# Compressor.net
KiCad netlist of a schematic drawn in Altium Designer
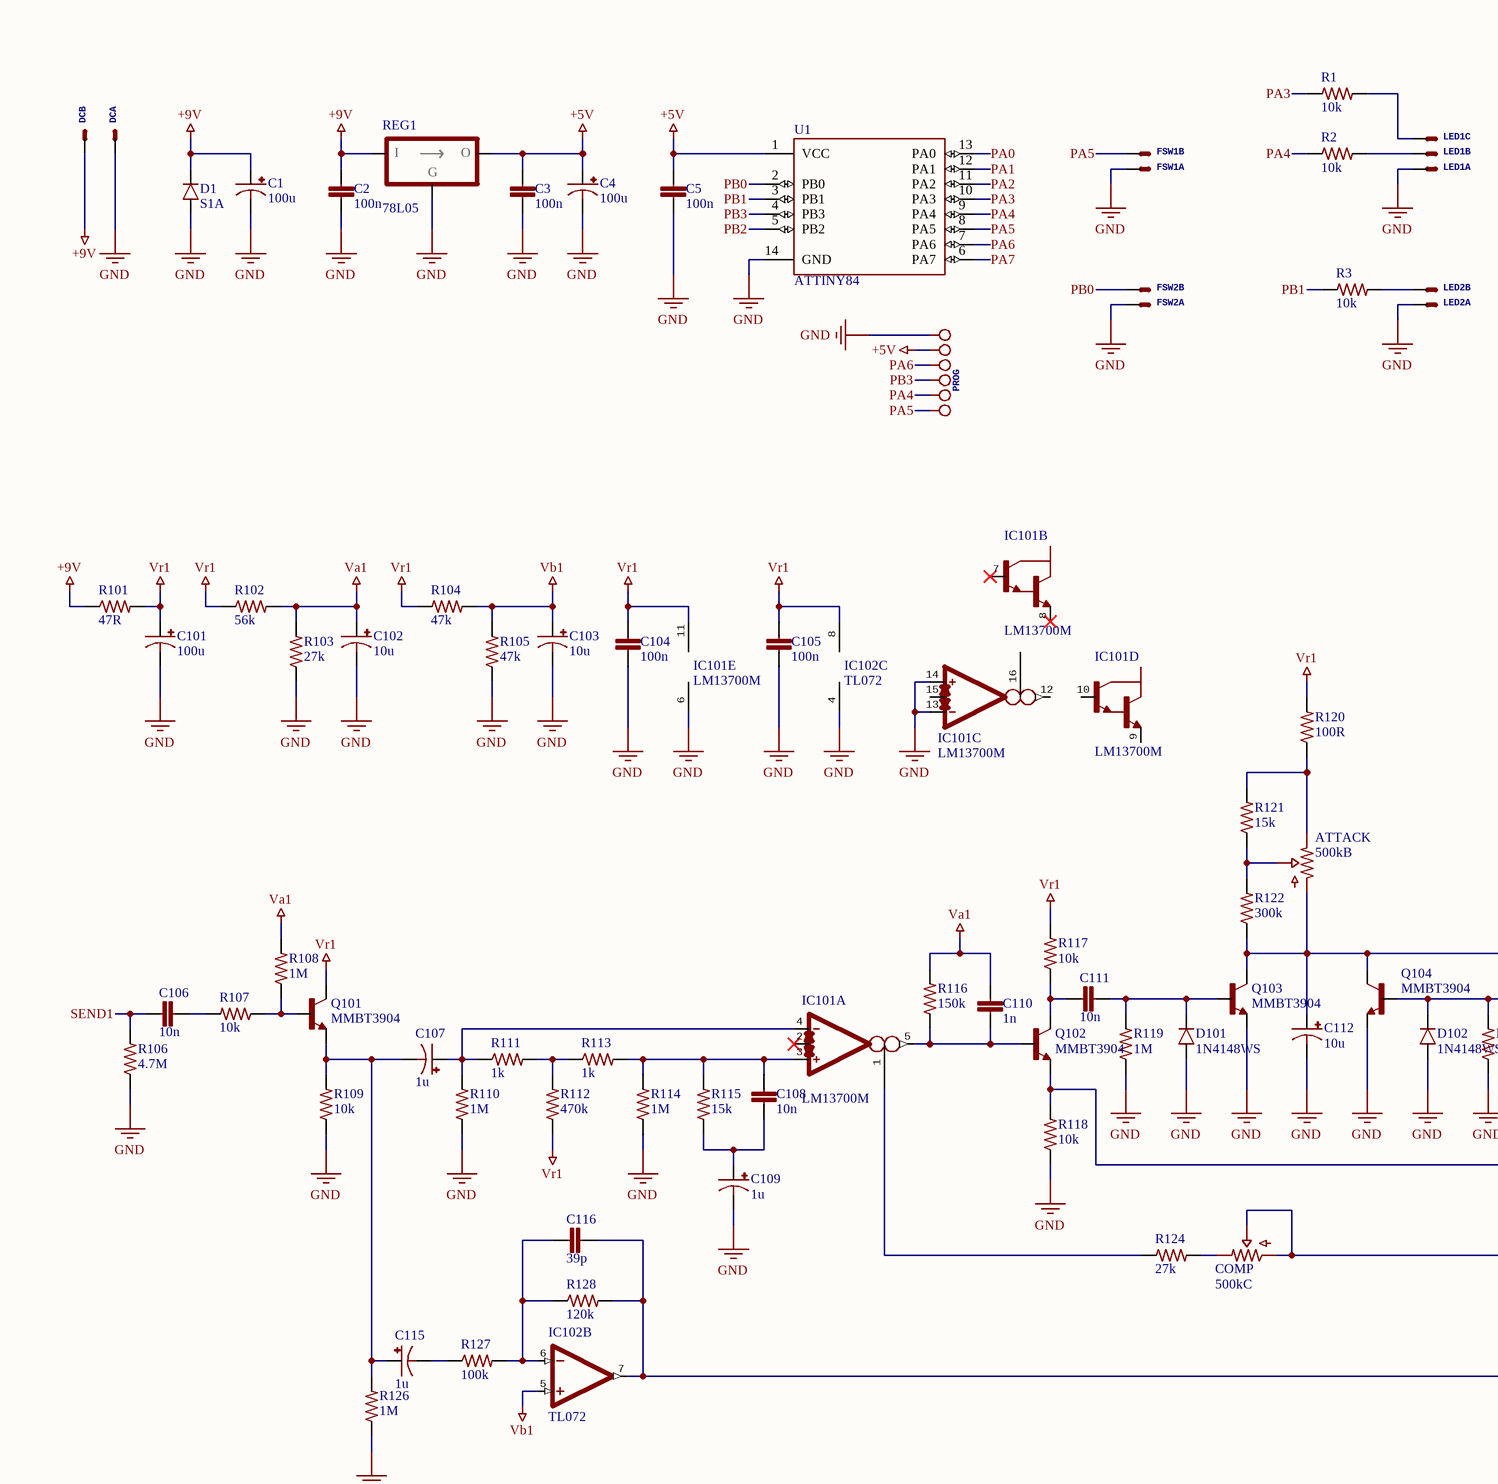
[diagram p0: Compressor.SchDoc, top left]
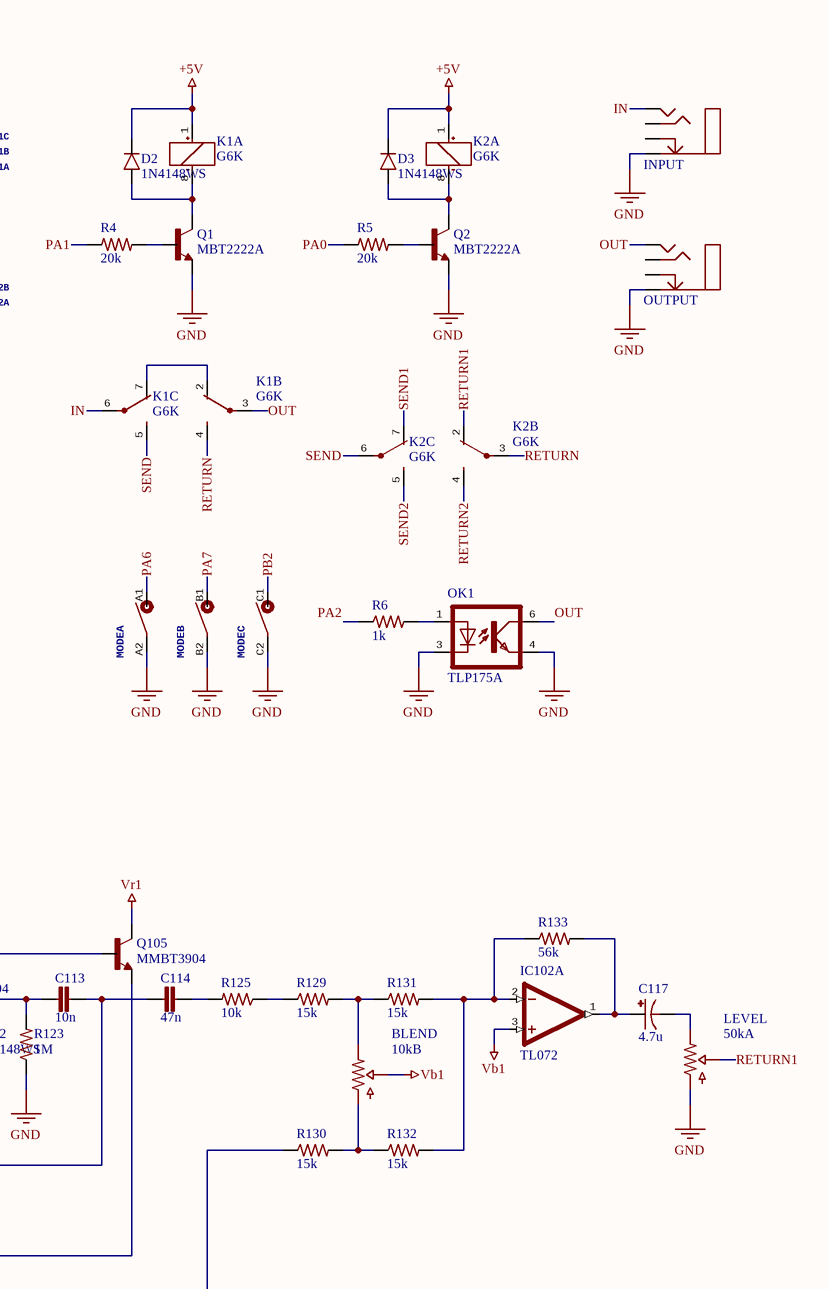
[diagram p1: Compressor.SchDoc, top right]
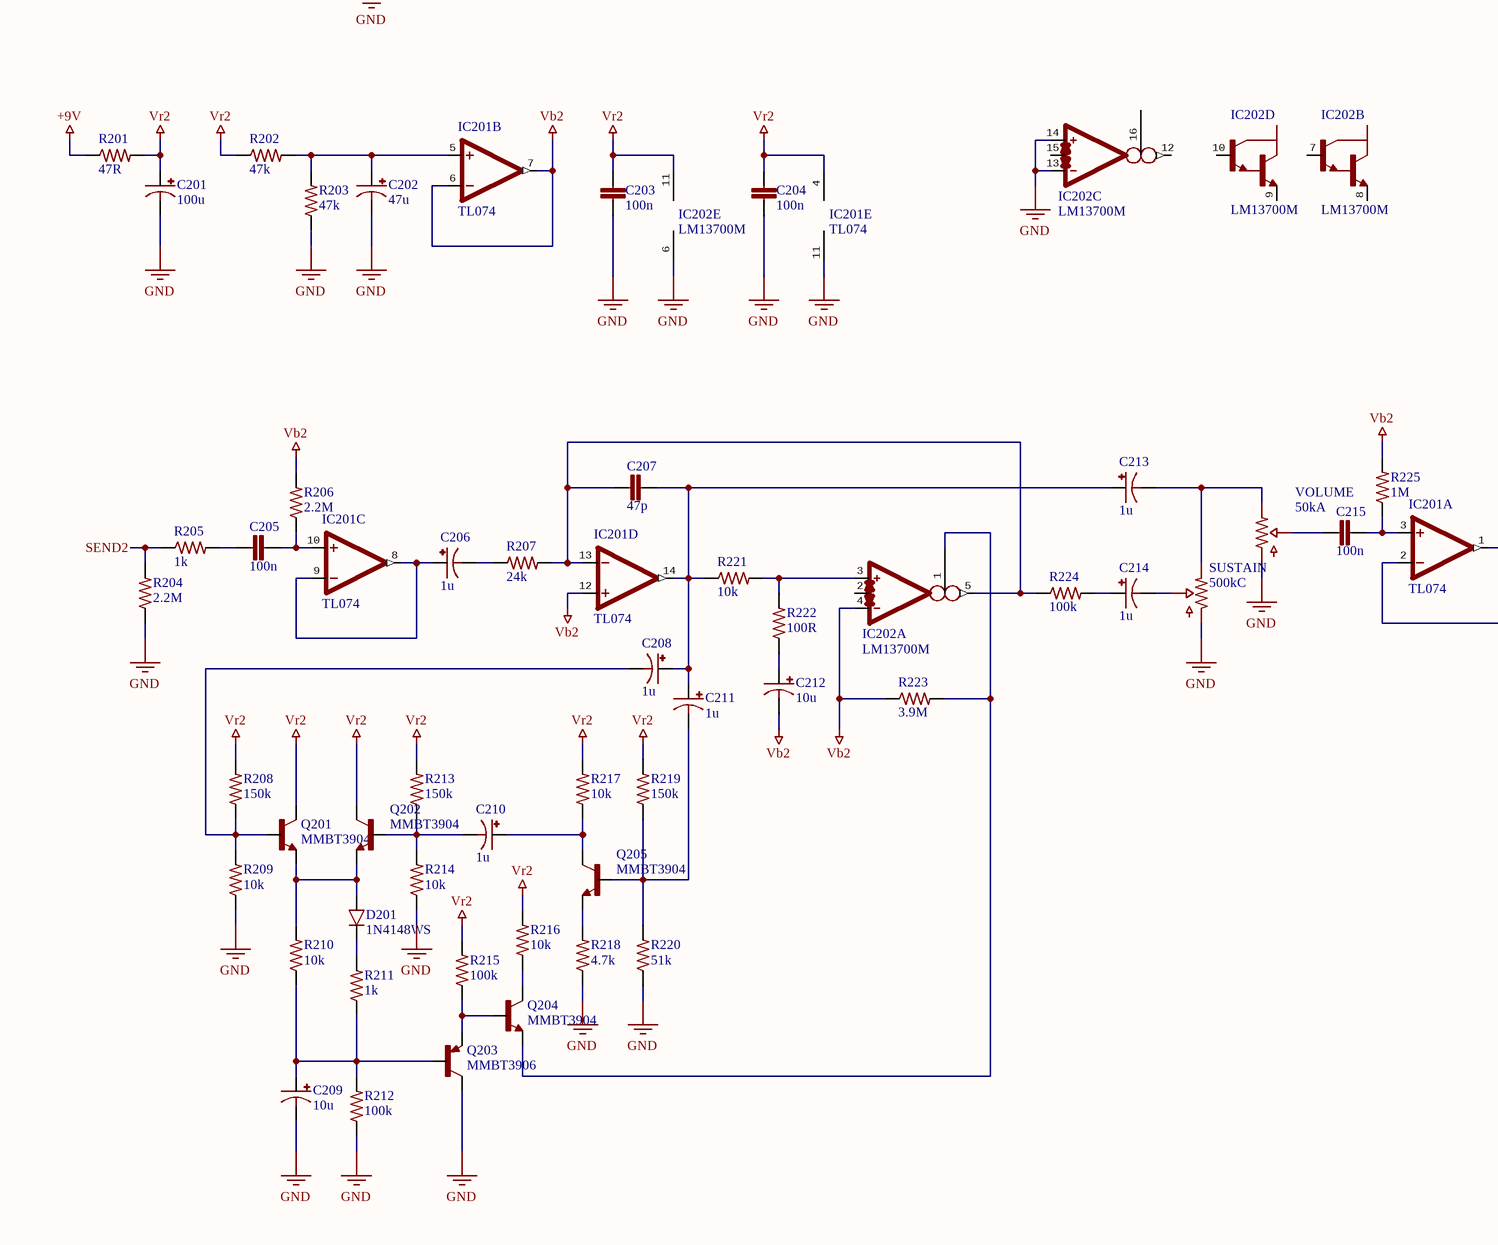
[diagram p2: Compressor.SchDoc, bottom left]
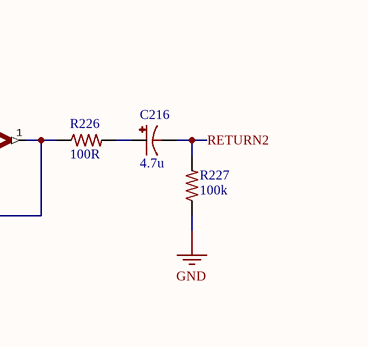
[diagram p3: Compressor.SchDoc, bottom right]

(export (version "E")
  (design (tool "Eeschema 10.0.6"))
  (components
    (comp (ref "ATTACK")
      (value "500kB")
      (footprint "ALPHA_9MM_TOP_NOMH")
      (description "500k Lin potentiometer round shaft")
      (libsource (lib "Pedals") (part "POT_500kB_ALPHA_9mm"))
    )
    (comp (ref "BLEND")
      (value "10kB")
      (footprint "ALPHA_9MM_TOP_NOMH")
      (description "10k Lin potentiometer round shaft")
      (libsource (lib "Pedals") (part "POT_10kB_ALPHA_9mm"))
    )
    (comp (ref "C1")
      (value "100u")
      (footprint "CAPAE_D")
      (description "CAP ALUM 100UF 25V SMD")
      (fields
        (field (name "MANUFACTURER") "Multicomp")
        (field (name "MANUFACTURER PART NUMBER") "MCVVT025M101EA6L")
      )
      (libsource (lib "Pedals SMD") (part "MCVVT025M101EA6L"))
    )
    (comp (ref "C2")
      (value "100n")
      (footprint "CHIP_0603")
      (description "CAP CER 100NF 50V X7R 0603")
      (fields
        (field (name "MANUFACTURER") "Multicomp")
        (field (name "MANUFACTURER PART NUMBER") "MC0603B104K500CT")
      )
      (libsource (lib "Pedals SMD") (part "MC0603B104K500CT"))
    )
    (comp (ref "C3")
      (value "100n")
      (footprint "CHIP_0603")
      (description "CAP CER 100NF 50V X7R 0603")
      (fields
        (field (name "MANUFACTURER") "Multicomp")
        (field (name "MANUFACTURER PART NUMBER") "MC0603B104K500CT")
      )
      (libsource (lib "Pedals SMD") (part "MC0603B104K500CT"))
    )
    (comp (ref "C4")
      (value "100u")
      (footprint "CAPAE_D")
      (description "CAP ALUM 100UF 25V SMD")
      (fields
        (field (name "MANUFACTURER") "Multicomp")
        (field (name "MANUFACTURER PART NUMBER") "MCVVT025M101EA6L")
      )
      (libsource (lib "Pedals SMD") (part "MCVVT025M101EA6L"))
    )
    (comp (ref "C5")
      (value "100n")
      (footprint "CHIP_0603")
      (description "CAP CER 100NF 50V X7R 0603")
      (fields
        (field (name "MANUFACTURER") "Multicomp")
        (field (name "MANUFACTURER PART NUMBER") "MC0603B104K500CT")
      )
      (libsource (lib "Pedals SMD") (part "MC0603B104K500CT"))
    )
    (comp (ref "C101")
      (value "100u")
      (footprint "CAPAE_D")
      (description "CAP ALUM 100UF 25V SMD")
      (fields
        (field (name "MANUFACTURER") "Multicomp")
        (field (name "MANUFACTURER PART NUMBER") "MCVVT025M101EA6L")
      )
      (libsource (lib "Pedals SMD") (part "MCVVT025M101EA6L"))
    )
    (comp (ref "C102")
      (value "10u")
      (footprint "CAPAE_B")
      (description "CAP ALUM 10UF 25V SMD")
      (fields
        (field (name "MANUFACTURER") "Multicomp")
        (field (name "MANUFACTURER PART NUMBER") "MCVVT025M100CA1L")
      )
      (libsource (lib "Pedals SMD") (part "MCVVT025M100CA1L"))
    )
    (comp (ref "C103")
      (value "10u")
      (footprint "CAPAE_B")
      (description "CAP ALUM 10UF 25V SMD")
      (fields
        (field (name "MANUFACTURER") "Multicomp")
        (field (name "MANUFACTURER PART NUMBER") "MCVVT025M100CA1L")
      )
      (libsource (lib "Pedals SMD") (part "MCVVT025M100CA1L"))
    )
    (comp (ref "C104")
      (value "100n")
      (footprint "CHIP_0603")
      (description "CAP CER 100NF 50V X7R 0603")
      (fields
        (field (name "MANUFACTURER") "Multicomp")
        (field (name "MANUFACTURER PART NUMBER") "MC0603B104K500CT")
      )
      (libsource (lib "Pedals SMD") (part "MC0603B104K500CT"))
    )
    (comp (ref "C105")
      (value "100n")
      (footprint "CHIP_0603")
      (description "CAP CER 100NF 50V X7R 0603")
      (fields
        (field (name "MANUFACTURER") "Multicomp")
        (field (name "MANUFACTURER PART NUMBER") "MC0603B104K500CT")
      )
      (libsource (lib "Pedals SMD") (part "MC0603B104K500CT"))
    )
    (comp (ref "C106")
      (value "10n")
      (footprint "CHIP_0603")
      (description "CAP CER 10NF 50V C0G/NP0 0603")
      (fields
        (field (name "MANUFACTURER") "Murata")
        (field (name "MANUFACTURER PART NUMBER") "GRM1885C1H103JA01D")
      )
      (libsource (lib "Pedals SMD") (part "GRM1885C1H103JA01D"))
    )
    (comp (ref "C107")
      (value "1u")
      (footprint "CAPAE_B")
      (description "CAP ALUM 1UF 50V LESR SMD")
      (fields
        (field (name "MANUFACTURER") "Panasonic")
        (field (name "MANUFACTURER PART NUMBER") "EEEFC1H1R0R")
      )
      (libsource (lib "") (part "EEEFC1H1R0R_1"))
    )
    (comp (ref "C108")
      (value "10n")
      (footprint "CHIP_0603")
      (description "CAP CER 10NF 50V C0G/NP0 0603")
      (fields
        (field (name "MANUFACTURER") "Murata")
        (field (name "MANUFACTURER PART NUMBER") "GRM1885C1H103JA01D")
      )
      (libsource (lib "") (part "GRM1885C1H103JA01D_1"))
    )
    (comp (ref "C109")
      (value "1u")
      (footprint "TAN_1206")
      (description "CAP TANT 1UF 16V")
      (fields
        (field (name "MANUFACTURER") "KEMET")
        (field (name "MANUFACTURER PART NUMBER") "T491A105K016AT")
      )
      (libsource (lib "Pedals SMD") (part "T491A105K016AT"))
    )
    (comp (ref "C110")
      (value "1n")
      (footprint "CHIP_0603")
      (description "CAP CER 1NF 50V C0G/NP0 0603")
      (fields
        (field (name "MANUFACTURER") "Murata")
        (field (name "MANUFACTURER PART NUMBER") "GRM1885C1H102JA01D")
      )
      (libsource (lib "Pedals SMD") (part "GRM1885C1H102JA01D"))
    )
    (comp (ref "C111")
      (value "10n")
      (footprint "CHIP_0603")
      (description "CAP CER 10NF 50V C0G/NP0 0603")
      (fields
        (field (name "MANUFACTURER") "Murata")
        (field (name "MANUFACTURER PART NUMBER") "GRM1885C1H103JA01D")
      )
      (libsource (lib "Pedals SMD") (part "GRM1885C1H103JA01D"))
    )
    (comp (ref "C112")
      (value "10u")
      (footprint "TAN_1206")
      (description "CAP TANT 10UF 16V")
      (fields
        (field (name "MANUFACTURER") "KEMET")
        (field (name "MANUFACTURER PART NUMBER") "T491A106K016AT")
      )
      (libsource (lib "Pedals SMD") (part "T491A106K016AT"))
    )
    (comp (ref "C113")
      (value "10n")
      (footprint "CHIP_0603")
      (description "CAP CER 10NF 50V C0G/NP0 0603")
      (fields
        (field (name "MANUFACTURER") "Murata")
        (field (name "MANUFACTURER PART NUMBER") "GRM1885C1H103JA01D")
      )
      (libsource (lib "Pedals SMD") (part "GRM1885C1H103JA01D"))
    )
    (comp (ref "C114")
      (value "47n")
      (footprint "CHIP_1206")
      (description "CAP CER 47NF 50V C0G/NP0 1206")
      (fields
        (field (name "MANUFACTURER") "Murata")
        (field (name "MANUFACTURER PART NUMBER") "GCM31M5C1H473JA16L")
      )
      (libsource (lib "Pedals SMD") (part "GCM31M5C1H473JA16L"))
    )
    (comp (ref "C115")
      (value "1u")
      (footprint "CAPAE_B")
      (description "CAP ALUM 1UF 50V LESR SMD")
      (fields
        (field (name "MANUFACTURER") "Panasonic")
        (field (name "MANUFACTURER PART NUMBER") "EEEFC1H1R0R")
      )
      (libsource (lib "Pedals SMD") (part "EEEFC1H1R0R"))
    )
    (comp (ref "C116")
      (value "39p")
      (footprint "CHIP_0603")
      (description "CAP CER 39PF 50V C0G/NP0 0603")
      (fields
        (field (name "MANUFACTURER") "Multicomp")
        (field (name "MANUFACTURER PART NUMBER") "MC0603N390J500CT")
      )
      (libsource (lib "Pedals SMD") (part "MC0603N390J500CT"))
    )
    (comp (ref "C117")
      (value "4.7u")
      (footprint "CAPAE_C")
      (description "CAP ALUM 4.7UF 50V LESR SMD")
      (fields
        (field (name "MANUFACTURER") "Panasonic")
        (field (name "MANUFACTURER PART NUMBER") "EEEFC1H4R7R")
      )
      (libsource (lib "Pedals SMD") (part "EEEFC1H4R7R"))
    )
    (comp (ref "C201")
      (value "100u")
      (footprint "CAPAE_D")
      (description "CAP ALUM 100UF 25V SMD")
      (fields
        (field (name "MANUFACTURER") "Multicomp")
        (field (name "MANUFACTURER PART NUMBER") "MCVVT025M101EA6L")
      )
      (libsource (lib "Pedals SMD") (part "MCVVT025M101EA6L"))
    )
    (comp (ref "C202")
      (value "47u")
      (footprint "CAPAE_D")
      (description "CAP ALUM 47UF 25V SMD")
      (fields
        (field (name "MANUFACTURER") "Multicomp")
        (field (name "MANUFACTURER PART NUMBER") "MCVVT025M470EA1L")
      )
      (libsource (lib "Pedals SMD") (part "MCVVT025M470EA1L"))
    )
    (comp (ref "C203")
      (value "100n")
      (footprint "CHIP_0603")
      (description "CAP CER 100NF 50V X7R 0603")
      (fields
        (field (name "MANUFACTURER") "Multicomp")
        (field (name "MANUFACTURER PART NUMBER") "MC0603B104K500CT")
      )
      (libsource (lib "Pedals SMD") (part "MC0603B104K500CT"))
    )
    (comp (ref "C204")
      (value "100n")
      (footprint "CHIP_0603")
      (description "CAP CER 100NF 50V X7R 0603")
      (fields
        (field (name "MANUFACTURER") "Multicomp")
        (field (name "MANUFACTURER PART NUMBER") "MC0603B104K500CT")
      )
      (libsource (lib "Pedals SMD") (part "MC0603B104K500CT"))
    )
    (comp (ref "C205")
      (value "100n")
      (footprint "CHIP_1206")
      (description "CAP CER 100NF 50V C0G/NP0 1206")
      (fields
        (field (name "MANUFACTURER") "Murata")
        (field (name "MANUFACTURER PART NUMBER") "GRM31C5C1H104JA01L")
      )
      (libsource (lib "Pedals SMD") (part "GRM31C5C1H104JA01L"))
    )
    (comp (ref "C206")
      (value "1u")
      (footprint "CAPAE_B")
      (description "CAP ALUM 1UF 50V LESR SMD")
      (fields
        (field (name "MANUFACTURER") "Panasonic")
        (field (name "MANUFACTURER PART NUMBER") "EEEFC1H1R0R")
      )
      (libsource (lib "Pedals SMD") (part "EEEFC1H1R0R"))
    )
    (comp (ref "C207")
      (value "47p")
      (footprint "CHIP_0603")
      (description "CAP CER 47PF 50V C0G/NP0 0603")
      (fields
        (field (name "MANUFACTURER") "Multicomp")
        (field (name "MANUFACTURER PART NUMBER") "MC0603N470J500CT")
      )
      (libsource (lib "Pedals SMD") (part "MC0603N470J500CT"))
    )
    (comp (ref "C208")
      (value "1u")
      (footprint "CAPAE_B")
      (description "CAP ALUM 1UF 50V LESR SMD")
      (fields
        (field (name "MANUFACTURER") "Panasonic")
        (field (name "MANUFACTURER PART NUMBER") "EEEFC1H1R0R")
      )
      (libsource (lib "") (part "EEEFC1H1R0R_2"))
    )
    (comp (ref "C209")
      (value "10u")
      (footprint "TAN_1206")
      (description "CAP TANT 10UF 16V")
      (fields
        (field (name "MANUFACTURER") "KEMET")
        (field (name "MANUFACTURER PART NUMBER") "T491A106K016AT")
      )
      (libsource (lib "Pedals SMD") (part "T491A106K016AT"))
    )
    (comp (ref "C210")
      (value "1u")
      (footprint "CAPAE_B")
      (description "CAP ALUM 1UF 50V LESR SMD")
      (fields
        (field (name "MANUFACTURER") "Panasonic")
        (field (name "MANUFACTURER PART NUMBER") "EEEFC1H1R0R")
      )
      (libsource (lib "") (part "EEEFC1H1R0R_2"))
    )
    (comp (ref "C211")
      (value "1u")
      (footprint "CAPAE_B")
      (description "CAP ALUM 1UF 50V LESR SMD")
      (fields
        (field (name "MANUFACTURER") "Panasonic")
        (field (name "MANUFACTURER PART NUMBER") "EEEFC1H1R0R")
      )
      (libsource (lib "") (part "EEEFC1H1R0R_3"))
    )
    (comp (ref "C212")
      (value "10u")
      (footprint "TAN_1206")
      (description "CAP TANT 10UF 16V")
      (fields
        (field (name "MANUFACTURER") "KEMET")
        (field (name "MANUFACTURER PART NUMBER") "T491A106K016AT")
      )
      (libsource (lib "Pedals SMD") (part "T491A106K016AT"))
    )
    (comp (ref "C213")
      (value "1u")
      (footprint "CAPAE_B")
      (description "CAP ALUM 1UF 50V LESR SMD")
      (fields
        (field (name "MANUFACTURER") "Panasonic")
        (field (name "MANUFACTURER PART NUMBER") "EEEFC1H1R0R")
      )
      (libsource (lib "Pedals SMD") (part "EEEFC1H1R0R"))
    )
    (comp (ref "C214")
      (value "1u")
      (footprint "CAPAE_B")
      (description "CAP ALUM 1UF 50V LESR SMD")
      (fields
        (field (name "MANUFACTURER") "Panasonic")
        (field (name "MANUFACTURER PART NUMBER") "EEEFC1H1R0R")
      )
      (libsource (lib "Pedals SMD") (part "EEEFC1H1R0R"))
    )
    (comp (ref "C215")
      (value "100n")
      (footprint "CHIP_1206")
      (description "CAP CER 100NF 50V C0G/NP0 1206")
      (fields
        (field (name "MANUFACTURER") "Murata")
        (field (name "MANUFACTURER PART NUMBER") "GRM31C5C1H104JA01L")
      )
      (libsource (lib "Pedals SMD") (part "GRM31C5C1H104JA01L"))
    )
    (comp (ref "C216")
      (value "4.7u")
      (footprint "CAPAE_C")
      (description "CAP ALUM 4.7UF 50V LESR SMD")
      (fields
        (field (name "MANUFACTURER") "Panasonic")
        (field (name "MANUFACTURER PART NUMBER") "EEEFC1H4R7R")
      )
      (libsource (lib "Pedals SMD") (part "EEEFC1H4R7R"))
    )
    (comp (ref "COMP")
      (value "500kC")
      (footprint "ALPHA_9MM_TOP_NOMH")
      (description "500k Anti Log potentiometer round shaft")
      (libsource (lib "Pedals") (part "POT_500kC_ALPHA_9mm"))
    )
    (comp (ref "D1")
      (value "S1A")
      (footprint "DO214")
      (description "DIODE GEN PURP 50V 1A SMA")
      (fields (field (name "MANUFACTURER") "ON Semiconductor / Fairchild"))
      (libsource (lib "Pedals SMD") (part "S1A"))
    )
    (comp (ref "D2")
      (value "1N4148WS")
      (footprint "SOD323")
      (description "DIODE GEN PURP 75V 150MA SOD323F")
      (fields (field (name "MANUFACTURER") "ON Semiconductor / Fairchild"))
      (libsource (lib "Pedals SMD") (part "1N4148WS"))
    )
    (comp (ref "D3")
      (value "1N4148WS")
      (footprint "SOD323")
      (description "DIODE GEN PURP 75V 150MA SOD323F")
      (fields (field (name "MANUFACTURER") "ON Semiconductor / Fairchild"))
      (libsource (lib "Pedals SMD") (part "1N4148WS"))
    )
    (comp (ref "D101")
      (value "1N4148WS")
      (footprint "SOD323")
      (description "DIODE GEN PURP 75V 150MA SOD323F")
      (fields (field (name "MANUFACTURER") "ON Semiconductor / Fairchild"))
      (libsource (lib "Pedals SMD") (part "1N4148WS"))
    )
    (comp (ref "D102")
      (value "1N4148WS")
      (footprint "SOD323")
      (description "DIODE GEN PURP 75V 150MA SOD323F")
      (fields (field (name "MANUFACTURER") "ON Semiconductor / Fairchild"))
      (libsource (lib "Pedals SMD") (part "1N4148WS"))
    )
    (comp (ref "D201")
      (value "1N4148WS")
      (footprint "SOD323")
      (description "DIODE GEN PURP 75V 150MA SOD323F")
      (fields (field (name "MANUFACTURER") "ON Semiconductor / Fairchild"))
      (libsource (lib "Pedals SMD") (part "1N4148WS"))
    )
    (comp (ref "DC")
      (value "J_JST-XH-02")
      (footprint "JST-XH-02")
      (description "2 Pins male XH header")
      (libsource (lib "Pedals") (part "J_JST-XH-02"))
    )
    (comp (ref "FSW1")
      (value "~")
      (footprint "JST-XH-02")
      (description "2 Pins male XH header")
      (libsource (lib "Pedals") (part "JST-XH-02"))
    )
    (comp (ref "FSW2")
      (value "~")
      (footprint "JST-XH-02")
      (description "2 Pins male XH header")
      (libsource (lib "Pedals") (part "JST-XH-02"))
    )
    (comp (ref "IC101")
      (value "LM13700M")
      (footprint "SO-16")
      (description "IC OPAMP TRANSCOND 2MHZ 16SOIC")
      (fields
        (field (name "MANUFACTURER") "TI National Semiconductor")
        (field (name "MANUFACTURER PART NUMBER") "LM13700M/NOPB")
      )
      (libsource (lib "Pedals SMD") (part "LM13700M/NOPB"))
    )
    (comp (ref "IC102")
      (value "TL072")
      (footprint "SO-8")
      (description "IC OPAMP JFET 4MHZ 8SO")
      (fields
        (field (name "MANUFACTURER") "STMicroelectronics")
        (field (name "MANUFACTURER PART NUMBER") "TL072CDT")
      )
      (libsource (lib "Pedals SMD") (part "TL072CDT"))
    )
    (comp (ref "IC201")
      (value "TL074")
      (footprint "SO-14")
      (description "IC OPAMP JFET 3MHZ 14SO")
      (fields
        (field (name "MANUFACTURER") "STMicroelectronics")
        (field (name "MANUFACTURER PART NUMBER") "TL074IDT")
      )
      (libsource (lib "Pedals SMD") (part "TL074IDT"))
    )
    (comp (ref "IC202")
      (value "LM13700M")
      (footprint "SO-16")
      (description "IC OPAMP TRANSCOND 2MHZ 16SOIC")
      (fields
        (field (name "MANUFACTURER") "TI National Semiconductor")
        (field (name "MANUFACTURER PART NUMBER") "LM13700M/NOPB")
      )
      (libsource (lib "Pedals SMD") (part "LM13700M/NOPB"))
    )
    (comp (ref "INPUT")
      (value "J_STEREO")
      (footprint "STEREO")
      (description "6.35mm stereo insulated socket jack PCB mounted")
      (libsource (lib "Pedals") (part "J_STEREO"))
    )
    (comp (ref "K1")
      (value "G6K")
      (footprint "G6K")
      (description "OMRON - G6K-2F 5DC - RELAY, SIGNAL, DPDT, 30VDC, 1A")
      (fields (field (name "MANUFACTURER") "Cliff") (field (name "MANUFACTURER PART NUMBER") "G6K-2F5DC"))
      (libsource (lib "") (part "G6K-2F5DC_1"))
    )
    (comp (ref "K2")
      (value "G6K")
      (footprint "G6K")
      (description "OMRON - G6K-2F 5DC - RELAY, SIGNAL, DPDT, 30VDC, 1A")
      (fields (field (name "MANUFACTURER") "Cliff") (field (name "MANUFACTURER PART NUMBER") "G6K-2F5DC"))
      (libsource (lib "") (part "G6K-2F5DC_3"))
    )
    (comp (ref "LED1")
      (value "J_JST-XH-03")
      (footprint "JST-XH-03")
      (description "3 Pins male XH header")
      (libsource (lib "Pedals") (part "J_JST-XH-03"))
    )
    (comp (ref "LED2")
      (value "~")
      (footprint "JST-XH-02")
      (description "2 Pins male XH header")
      (libsource (lib "Pedals") (part "JST-XH-02"))
    )
    (comp (ref "LEVEL")
      (value "50kA")
      (footprint "ALPHA_9MM_TOP_NOMH")
      (description "50k Log potentiometer round shaft")
      (libsource (lib "Pedals") (part "POT_50kA_ALPHA_9mm"))
    )
    (comp (ref "MODE")
      (value "DIP")
      (footprint "DIP_3WAY")
      (description "DIP Switch 3 way")
      (libsource (lib "Pedals") (part "SW_DIP_3WAY"))
    )
    (comp (ref "OK1")
      (value "TLP175A")
      (footprint "TLP175A")
      (description "Toshiba TLP175A AC Input MOSFET Output Optocoupler, Surface Mount, 4-Pin SOIC")
      (fields (field (name "MANUFACTURER") "Toshiba"))
      (libsource (lib "Pedals SMD") (part "TLP175A"))
    )
    (comp (ref "OUTPUT")
      (value "J_STEREO")
      (footprint "STEREO")
      (description "6.35mm stereo insulated socket jack PCB mounted")
      (libsource (lib "Pedals") (part "J_STEREO"))
    )
    (comp (ref "PROG")
      (value "J_HEADER_6PINS_FEM")
      (footprint "HEADER_6Pins_FEM")
      (description "5 Pins female header")
      (libsource (lib "Pedals") (part "J_HEADER_6PINS_FEM"))
    )
    (comp (ref "Q1")
      (value "MBT2222A")
      (footprint "SOT323")
      (description "TRANS NPN 40V 0.6A SOT323")
      (fields
        (field (name "MANUFACTURER") "ON Semiconductor")
        (field (name "MANUFACTURER PART NUMBER") "MMBT2222AWT1G")
      )
      (libsource (lib "Pedals SMD") (part "MMBT2222AWT1G"))
    )
    (comp (ref "Q2")
      (value "MBT2222A")
      (footprint "SOT323")
      (description "TRANS NPN 40V 0.6A SOT323")
      (fields
        (field (name "MANUFACTURER") "ON Semiconductor")
        (field (name "MANUFACTURER PART NUMBER") "MMBT2222AWT1G")
      )
      (libsource (lib "Pedals SMD") (part "MMBT2222AWT1G"))
    )
    (comp (ref "Q101")
      (value "MMBT3904")
      (footprint "SOT23")
      (description "TRANS NPN 40V 0.2A SOT23")
      (fields
        (field (name "MANUFACTURER") "ON Semiconductor")
        (field (name "MANUFACTURER PART NUMBER") "MMBT3904LT1G")
      )
      (libsource (lib "") (part "MMBT3904LT1G_1"))
    )
    (comp (ref "Q102")
      (value "MMBT3904")
      (footprint "SOT23")
      (description "TRANS NPN 40V 0.2A SOT23")
      (fields
        (field (name "MANUFACTURER") "ON Semiconductor")
        (field (name "MANUFACTURER PART NUMBER") "MMBT3904LT1G")
      )
      (libsource (lib "") (part "MMBT3904LT1G_1"))
    )
    (comp (ref "Q103")
      (value "MMBT3904")
      (footprint "SOT23")
      (description "TRANS NPN 40V 0.2A SOT23")
      (fields
        (field (name "MANUFACTURER") "ON Semiconductor")
        (field (name "MANUFACTURER PART NUMBER") "MMBT3904LT1G")
      )
      (libsource (lib "") (part "MMBT3904LT1G_1"))
    )
    (comp (ref "Q104")
      (value "MMBT3904")
      (footprint "SOT23")
      (description "TRANS NPN 40V 0.2A SOT23")
      (fields
        (field (name "MANUFACTURER") "ON Semiconductor")
        (field (name "MANUFACTURER PART NUMBER") "MMBT3904LT1G")
      )
      (libsource (lib "Pedals SMD") (part "MMBT3904LT1G"))
    )
    (comp (ref "Q105")
      (value "MMBT3904")
      (footprint "SOT23")
      (description "TRANS NPN 40V 0.2A SOT23")
      (fields
        (field (name "MANUFACTURER") "ON Semiconductor")
        (field (name "MANUFACTURER PART NUMBER") "MMBT3904LT1G")
      )
      (libsource (lib "") (part "MMBT3904LT1G_1"))
    )
    (comp (ref "Q201")
      (value "MMBT3904")
      (footprint "SOT23")
      (description "TRANS NPN 40V 0.2A SOT23")
      (fields
        (field (name "MANUFACTURER") "ON Semiconductor")
        (field (name "MANUFACTURER PART NUMBER") "MMBT3904LT1G")
      )
      (libsource (lib "") (part "MMBT3904LT1G_1"))
    )
    (comp (ref "Q202")
      (value "MMBT3904")
      (footprint "SOT23")
      (description "TRANS NPN 40V 0.2A SOT23")
      (fields
        (field (name "MANUFACTURER") "ON Semiconductor")
        (field (name "MANUFACTURER PART NUMBER") "MMBT3904LT1G")
      )
      (libsource (lib "Pedals SMD") (part "MMBT3904LT1G"))
    )
    (comp (ref "Q203")
      (value "MMBT3906")
      (footprint "SOT23")
      (description "TRANS PNP 40V 0.2A SOT23")
      (fields
        (field (name "MANUFACTURER") "ON Semiconductor")
        (field (name "MANUFACTURER PART NUMBER") "MMBT3906LT1G")
      )
      (libsource (lib "Pedals SMD") (part "MMBT3906LT1G"))
    )
    (comp (ref "Q204")
      (value "MMBT3904")
      (footprint "SOT23")
      (description "TRANS NPN 40V 0.2A SOT23")
      (fields
        (field (name "MANUFACTURER") "ON Semiconductor")
        (field (name "MANUFACTURER PART NUMBER") "MMBT3904LT1G")
      )
      (libsource (lib "") (part "MMBT3904LT1G_1"))
    )
    (comp (ref "Q205")
      (value "MMBT3904")
      (footprint "SOT23")
      (description "TRANS NPN 40V 0.2A SOT23")
      (fields
        (field (name "MANUFACTURER") "ON Semiconductor")
        (field (name "MANUFACTURER PART NUMBER") "MMBT3904LT1G")
      )
      (libsource (lib "Pedals SMD") (part "MMBT3904LT1G"))
    )
    (comp (ref "R1")
      (value "10k")
      (footprint "CHIP_R_1206")
      (description "RES SMD 10K OHM 1% 1/4W 1206")
      (fields
        (field (name "MANUFACTURER") "Vishay")
        (field (name "MANUFACTURER PART NUMBER") "CRCW120610K0FKEA")
      )
      (libsource (lib "Pedals SMD") (part "CRCW120610K0FKEA"))
    )
    (comp (ref "R2")
      (value "10k")
      (footprint "CHIP_R_1206")
      (description "RES SMD 10K OHM 1% 1/4W 1206")
      (fields
        (field (name "MANUFACTURER") "Vishay")
        (field (name "MANUFACTURER PART NUMBER") "CRCW120610K0FKEA")
      )
      (libsource (lib "Pedals SMD") (part "CRCW120610K0FKEA"))
    )
    (comp (ref "R3")
      (value "10k")
      (footprint "CHIP_R_1206")
      (description "RES SMD 10K OHM 1% 1/4W 1206")
      (fields
        (field (name "MANUFACTURER") "Vishay")
        (field (name "MANUFACTURER PART NUMBER") "CRCW120610K0FKEA")
      )
      (libsource (lib "Pedals SMD") (part "CRCW120610K0FKEA"))
    )
    (comp (ref "R4")
      (value "20k")
      (footprint "CHIP_R_0603")
      (description "RES SMD 20K OHM 1% 1/10W 0603")
      (fields
        (field (name "MANUFACTURER") "Vishay")
        (field (name "MANUFACTURER PART NUMBER") "CRCW060320K0FKEA")
      )
      (libsource (lib "Pedals SMD") (part "CRCW060320K0FKEA"))
    )
    (comp (ref "R5")
      (value "20k")
      (footprint "CHIP_R_0603")
      (description "RES SMD 20K OHM 1% 1/10W 0603")
      (fields
        (field (name "MANUFACTURER") "Vishay")
        (field (name "MANUFACTURER PART NUMBER") "CRCW060320K0FKEA")
      )
      (libsource (lib "Pedals SMD") (part "CRCW060320K0FKEA"))
    )
    (comp (ref "R6")
      (value "1k")
      (footprint "CHIP_R_0603")
      (description "RES SMD 1K OHM 1% 1/10W 0603")
      (fields
        (field (name "MANUFACTURER") "Vishay Dale")
        (field (name "MANUFACTURER PART NUMBER") "CRCW06031K00FKEA")
      )
      (libsource (lib "Pedals SMD") (part "CRCW06031K00FKEA"))
    )
    (comp (ref "R101")
      (value "47R")
      (footprint "CHIP_R_1206")
      (description "RES SMD 47 OHM 1% 1/4W 1206")
      (fields
        (field (name "MANUFACTURER") "Vishay")
        (field (name "MANUFACTURER PART NUMBER") "CRCW120647R0FKEA")
      )
      (libsource (lib "Pedals SMD") (part "CRCW120647R0FKEA"))
    )
    (comp (ref "R102")
      (value "56k")
      (footprint "CHIP_R_1206")
      (description "RES SMD 56K OHM 1% 1/4W 1206")
      (fields
        (field (name "MANUFACTURER") "Vishay")
        (field (name "MANUFACTURER PART NUMBER") "CRCW120656K0FKEA")
      )
      (libsource (lib "Pedals SMD") (part "CRCW120656K0FKEA"))
    )
    (comp (ref "R103")
      (value "27k")
      (footprint "CHIP_R_1206")
      (description "RES SMD 27K OHM 1% 1/4W 1206")
      (fields
        (field (name "MANUFACTURER") "Vishay")
        (field (name "MANUFACTURER PART NUMBER") "CRCW120627K0FKEA")
      )
      (libsource (lib "Pedals SMD") (part "CRCW120627K0FKEA"))
    )
    (comp (ref "R104")
      (value "47k")
      (footprint "CHIP_R_1206")
      (description "RES SMD 47K OHM 1% 1/4W 1206")
      (fields
        (field (name "MANUFACTURER") "Vishay")
        (field (name "MANUFACTURER PART NUMBER") "CRCW120647K0FKEA")
      )
      (libsource (lib "Pedals SMD") (part "CRCW120647K0FKEA"))
    )
    (comp (ref "R105")
      (value "47k")
      (footprint "CHIP_R_1206")
      (description "RES SMD 47K OHM 1% 1/4W 1206")
      (fields
        (field (name "MANUFACTURER") "Vishay")
        (field (name "MANUFACTURER PART NUMBER") "CRCW120647K0FKEA")
      )
      (libsource (lib "Pedals SMD") (part "CRCW120647K0FKEA"))
    )
    (comp (ref "R106")
      (value "4.7M")
      (footprint "CHIP_R_0603")
      (description "RES SMD 4.7M OHM 1% 1/10W 0603")
      (fields
        (field (name "MANUFACTURER") "Vishay")
        (field (name "MANUFACTURER PART NUMBER") "CRCW06034M70FKEA")
      )
      (libsource (lib "Pedals SMD") (part "CRCW06034M70FKEA"))
    )
    (comp (ref "R107")
      (value "10k")
      (footprint "CHIP_R_0603")
      (description "RES SMD 10K OHM 1% 1/10W 0603")
      (fields
        (field (name "MANUFACTURER") "Vishay")
        (field (name "MANUFACTURER PART NUMBER") "CRCW060310K0FKEA")
      )
      (libsource (lib "Pedals SMD") (part "CRCW060310K0FKEA"))
    )
    (comp (ref "R108")
      (value "1M")
      (footprint "CHIP_R_0603")
      (description "RES SMD 1M OHM 1% 1/10W 0603")
      (fields
        (field (name "MANUFACTURER") "Vishay")
        (field (name "MANUFACTURER PART NUMBER") "CRCW06031M00FKEA")
      )
      (libsource (lib "Pedals SMD") (part "CRCW06031M00FKEA"))
    )
    (comp (ref "R109")
      (value "10k")
      (footprint "CHIP_R_0603")
      (description "RES SMD 10K OHM 1% 1/10W 0603")
      (fields
        (field (name "MANUFACTURER") "Vishay")
        (field (name "MANUFACTURER PART NUMBER") "CRCW060310K0FKEA")
      )
      (libsource (lib "Pedals SMD") (part "CRCW060310K0FKEA"))
    )
    (comp (ref "R110")
      (value "1M")
      (footprint "CHIP_R_0603")
      (description "RES SMD 1M OHM 1% 1/10W 0603")
      (fields
        (field (name "MANUFACTURER") "Vishay")
        (field (name "MANUFACTURER PART NUMBER") "CRCW06031M00FKEA")
      )
      (libsource (lib "Pedals SMD") (part "CRCW06031M00FKEA"))
    )
    (comp (ref "R111")
      (value "1k")
      (footprint "CHIP_R_0603")
      (description "RES SMD 1K OHM 1% 1/10W 0603")
      (fields
        (field (name "MANUFACTURER") "Vishay Dale")
        (field (name "MANUFACTURER PART NUMBER") "CRCW06031K00FKEA")
      )
      (libsource (lib "Pedals SMD") (part "CRCW06031K00FKEA"))
    )
    (comp (ref "R112")
      (value "470k")
      (footprint "CHIP_R_0603")
      (description "RES SMD 470K OHM 1% 1/10W 0603")
      (fields
        (field (name "MANUFACTURER") "Vishay")
        (field (name "MANUFACTURER PART NUMBER") "CRCW0603470KFKEA")
      )
      (libsource (lib "Pedals SMD") (part "CRCW0603470KFKEA"))
    )
    (comp (ref "R113")
      (value "1k")
      (footprint "CHIP_R_0603")
      (description "RES SMD 1K OHM 1% 1/10W 0603")
      (fields
        (field (name "MANUFACTURER") "Vishay Dale")
        (field (name "MANUFACTURER PART NUMBER") "CRCW06031K00FKEA")
      )
      (libsource (lib "Pedals SMD") (part "CRCW06031K00FKEA"))
    )
    (comp (ref "R114")
      (value "1M")
      (footprint "CHIP_R_0603")
      (description "RES SMD 1M OHM 1% 1/10W 0603")
      (fields
        (field (name "MANUFACTURER") "Vishay")
        (field (name "MANUFACTURER PART NUMBER") "CRCW06031M00FKEA")
      )
      (libsource (lib "Pedals SMD") (part "CRCW06031M00FKEA"))
    )
    (comp (ref "R115")
      (value "15k")
      (footprint "CHIP_R_0603")
      (description "RES SMD 15K OHM 1% 1/10W 0603")
      (fields
        (field (name "MANUFACTURER") "Vishay")
        (field (name "MANUFACTURER PART NUMBER") "CRCW060315K0FKEA")
      )
      (libsource (lib "Pedals SMD") (part "CRCW060315K0FKEA"))
    )
    (comp (ref "R116")
      (value "150k")
      (footprint "CHIP_R_0603")
      (description "RES SMD 150K OHM 1% 1/10W 0603")
      (fields
        (field (name "MANUFACTURER") "Vishay")
        (field (name "MANUFACTURER PART NUMBER") "CRCW0603150KFKEA")
      )
      (libsource (lib "Pedals SMD") (part "CRCW0603150KFKEA"))
    )
    (comp (ref "R117")
      (value "10k")
      (footprint "CHIP_R_0603")
      (description "RES SMD 10K OHM 1% 1/10W 0603")
      (fields
        (field (name "MANUFACTURER") "Vishay")
        (field (name "MANUFACTURER PART NUMBER") "CRCW060310K0FKEA")
      )
      (libsource (lib "Pedals SMD") (part "CRCW060310K0FKEA"))
    )
    (comp (ref "R118")
      (value "10k")
      (footprint "CHIP_R_0603")
      (description "RES SMD 10K OHM 1% 1/10W 0603")
      (fields
        (field (name "MANUFACTURER") "Vishay")
        (field (name "MANUFACTURER PART NUMBER") "CRCW060310K0FKEA")
      )
      (libsource (lib "Pedals SMD") (part "CRCW060310K0FKEA"))
    )
    (comp (ref "R119")
      (value "1M")
      (footprint "CHIP_R_0603")
      (description "RES SMD 1M OHM 1% 1/10W 0603")
      (fields
        (field (name "MANUFACTURER") "Vishay")
        (field (name "MANUFACTURER PART NUMBER") "CRCW06031M00FKEA")
      )
      (libsource (lib "Pedals SMD") (part "CRCW06031M00FKEA"))
    )
    (comp (ref "R120")
      (value "100R")
      (footprint "CHIP_R_0603")
      (description "RES SMD 100 OHM 1% 1/10W 0603")
      (fields
        (field (name "MANUFACTURER") "Vishay Dale")
        (field (name "MANUFACTURER PART NUMBER") "CRCW0603100RFKEA")
      )
      (libsource (lib "Pedals SMD") (part "CRCW0603100RFKEA"))
    )
    (comp (ref "R121")
      (value "15k")
      (footprint "CHIP_R_0603")
      (description "RES SMD 15K OHM 1% 1/10W 0603")
      (fields
        (field (name "MANUFACTURER") "Vishay")
        (field (name "MANUFACTURER PART NUMBER") "CRCW060315K0FKEA")
      )
      (libsource (lib "Pedals SMD") (part "CRCW060315K0FKEA"))
    )
    (comp (ref "R122")
      (value "300k")
      (footprint "CHIP_R_0603")
      (description "RES SMD 300K OHM 1% 1/10W 0603")
      (fields
        (field (name "MANUFACTURER") "Vishay")
        (field (name "MANUFACTURER PART NUMBER") "CRCW0603300KFKEA")
      )
      (libsource (lib "Pedals SMD") (part "CRCW0603300KFKEA"))
    )
    (comp (ref "R123")
      (value "1M")
      (footprint "CHIP_R_0603")
      (description "RES SMD 1M OHM 1% 1/10W 0603")
      (fields
        (field (name "MANUFACTURER") "Vishay")
        (field (name "MANUFACTURER PART NUMBER") "CRCW06031M00FKEA")
      )
      (libsource (lib "Pedals SMD") (part "CRCW06031M00FKEA"))
    )
    (comp (ref "R124")
      (value "27k")
      (footprint "CHIP_R_0603")
      (description "RES SMD 27K OHM 1% 1/10W 0603")
      (fields
        (field (name "MANUFACTURER") "Vishay")
        (field (name "MANUFACTURER PART NUMBER") "CRCW060327K0FKEA")
      )
      (libsource (lib "Pedals SMD") (part "CRCW060327K0FKEA"))
    )
    (comp (ref "R125")
      (value "10k")
      (footprint "CHIP_R_0603")
      (description "RES SMD 10K OHM 1% 1/10W 0603")
      (fields
        (field (name "MANUFACTURER") "Vishay")
        (field (name "MANUFACTURER PART NUMBER") "CRCW060310K0FKEA")
      )
      (libsource (lib "Pedals SMD") (part "CRCW060310K0FKEA"))
    )
    (comp (ref "R126")
      (value "1M")
      (footprint "CHIP_R_0603")
      (description "RES SMD 1M OHM 1% 1/10W 0603")
      (fields
        (field (name "MANUFACTURER") "Vishay")
        (field (name "MANUFACTURER PART NUMBER") "CRCW06031M00FKEA")
      )
      (libsource (lib "Pedals SMD") (part "CRCW06031M00FKEA"))
    )
    (comp (ref "R127")
      (value "100k")
      (footprint "CHIP_R_0603")
      (description "RES SMD 100K OHM 1% 1/10W 0603")
      (fields
        (field (name "MANUFACTURER") "Vishay")
        (field (name "MANUFACTURER PART NUMBER") "CRCW0603100KFKEA")
      )
      (libsource (lib "Pedals SMD") (part "CRCW0603100KFKEA"))
    )
    (comp (ref "R128")
      (value "120k")
      (footprint "CHIP_R_0603")
      (description "RES SMD 120K OHM 1% 1/10W 0603")
      (fields
        (field (name "MANUFACTURER") "Vishay")
        (field (name "MANUFACTURER PART NUMBER") "CRCW0603120KFKEA")
      )
      (libsource (lib "Pedals SMD") (part "CRCW0603120KFKEA"))
    )
    (comp (ref "R129")
      (value "15k")
      (footprint "CHIP_R_0603")
      (description "RES SMD 15K OHM 1% 1/10W 0603")
      (fields
        (field (name "MANUFACTURER") "Vishay")
        (field (name "MANUFACTURER PART NUMBER") "CRCW060315K0FKEA")
      )
      (libsource (lib "Pedals SMD") (part "CRCW060315K0FKEA"))
    )
    (comp (ref "R130")
      (value "15k")
      (footprint "CHIP_R_0603")
      (description "RES SMD 15K OHM 1% 1/10W 0603")
      (fields
        (field (name "MANUFACTURER") "Vishay")
        (field (name "MANUFACTURER PART NUMBER") "CRCW060315K0FKEA")
      )
      (libsource (lib "Pedals SMD") (part "CRCW060315K0FKEA"))
    )
    (comp (ref "R131")
      (value "15k")
      (footprint "CHIP_R_0603")
      (description "RES SMD 15K OHM 1% 1/10W 0603")
      (fields
        (field (name "MANUFACTURER") "Vishay")
        (field (name "MANUFACTURER PART NUMBER") "CRCW060315K0FKEA")
      )
      (libsource (lib "Pedals SMD") (part "CRCW060315K0FKEA"))
    )
    (comp (ref "R132")
      (value "15k")
      (footprint "CHIP_R_0603")
      (description "RES SMD 15K OHM 1% 1/10W 0603")
      (fields
        (field (name "MANUFACTURER") "Vishay")
        (field (name "MANUFACTURER PART NUMBER") "CRCW060315K0FKEA")
      )
      (libsource (lib "Pedals SMD") (part "CRCW060315K0FKEA"))
    )
    (comp (ref "R133")
      (value "56k")
      (footprint "CHIP_R_0603")
      (description "RES SMD 56K OHM 1% 1/10W 0603")
      (fields
        (field (name "MANUFACTURER") "Vishay")
        (field (name "MANUFACTURER PART NUMBER") "CRCW060356K0FKEA")
      )
      (libsource (lib "Pedals SMD") (part "CRCW060356K0FKEA"))
    )
    (comp (ref "R201")
      (value "47R")
      (footprint "CHIP_R_1206")
      (description "RES SMD 47 OHM 1% 1/4W 1206")
      (fields
        (field (name "MANUFACTURER") "Vishay")
        (field (name "MANUFACTURER PART NUMBER") "CRCW120647R0FKEA")
      )
      (libsource (lib "Pedals SMD") (part "CRCW120647R0FKEA"))
    )
    (comp (ref "R202")
      (value "47k")
      (footprint "CHIP_R_1206")
      (description "RES SMD 47K OHM 1% 1/4W 1206")
      (fields
        (field (name "MANUFACTURER") "Vishay")
        (field (name "MANUFACTURER PART NUMBER") "CRCW120647K0FKEA")
      )
      (libsource (lib "Pedals SMD") (part "CRCW120647K0FKEA"))
    )
    (comp (ref "R203")
      (value "47k")
      (footprint "CHIP_R_1206")
      (description "RES SMD 47K OHM 1% 1/4W 1206")
      (fields
        (field (name "MANUFACTURER") "Vishay")
        (field (name "MANUFACTURER PART NUMBER") "CRCW120647K0FKEA")
      )
      (libsource (lib "Pedals SMD") (part "CRCW120647K0FKEA"))
    )
    (comp (ref "R204")
      (value "2.2M")
      (footprint "CHIP_R_0603")
      (description "RES SMD 2.2M OHM 1% 1/10W 0603")
      (fields
        (field (name "MANUFACTURER") "Vishay")
        (field (name "MANUFACTURER PART NUMBER") "CRCW06032M20FKEA")
      )
      (libsource (lib "Pedals SMD") (part "CRCW06032M20FKEA"))
    )
    (comp (ref "R205")
      (value "1k")
      (footprint "CHIP_R_0603")
      (description "RES SMD 1K OHM 1% 1/10W 0603")
      (fields
        (field (name "MANUFACTURER") "Vishay Dale")
        (field (name "MANUFACTURER PART NUMBER") "CRCW06031K00FKEA")
      )
      (libsource (lib "Pedals SMD") (part "CRCW06031K00FKEA"))
    )
    (comp (ref "R206")
      (value "2.2M")
      (footprint "CHIP_R_0603")
      (description "RES SMD 2.2M OHM 1% 1/10W 0603")
      (fields
        (field (name "MANUFACTURER") "Vishay")
        (field (name "MANUFACTURER PART NUMBER") "CRCW06032M20FKEA")
      )
      (libsource (lib "Pedals SMD") (part "CRCW06032M20FKEA"))
    )
    (comp (ref "R207")
      (value "24k")
      (footprint "CHIP_R_0603")
      (description "RES SMD 24K OHM 1% 1/10W 0603")
      (fields
        (field (name "MANUFACTURER") "Vishay")
        (field (name "MANUFACTURER PART NUMBER") "CRCW060324K0FKEA")
      )
      (libsource (lib "Pedals SMD") (part "CRCW060324K0FKEA"))
    )
    (comp (ref "R208")
      (value "150k")
      (footprint "CHIP_R_0603")
      (description "RES SMD 150K OHM 1% 1/10W 0603")
      (fields
        (field (name "MANUFACTURER") "Vishay")
        (field (name "MANUFACTURER PART NUMBER") "CRCW0603150KFKEA")
      )
      (libsource (lib "Pedals SMD") (part "CRCW0603150KFKEA"))
    )
    (comp (ref "R209")
      (value "10k")
      (footprint "CHIP_R_0603")
      (description "RES SMD 10K OHM 1% 1/10W 0603")
      (fields
        (field (name "MANUFACTURER") "Vishay")
        (field (name "MANUFACTURER PART NUMBER") "CRCW060310K0FKEA")
      )
      (libsource (lib "Pedals SMD") (part "CRCW060310K0FKEA"))
    )
    (comp (ref "R210")
      (value "10k")
      (footprint "CHIP_R_0603")
      (description "RES SMD 10K OHM 1% 1/10W 0603")
      (fields
        (field (name "MANUFACTURER") "Vishay")
        (field (name "MANUFACTURER PART NUMBER") "CRCW060310K0FKEA")
      )
      (libsource (lib "Pedals SMD") (part "CRCW060310K0FKEA"))
    )
    (comp (ref "R211")
      (value "1k")
      (footprint "CHIP_R_0603")
      (description "RES SMD 1K OHM 1% 1/10W 0603")
      (fields
        (field (name "MANUFACTURER") "Vishay Dale")
        (field (name "MANUFACTURER PART NUMBER") "CRCW06031K00FKEA")
      )
      (libsource (lib "Pedals SMD") (part "CRCW06031K00FKEA"))
    )
    (comp (ref "R212")
      (value "100k")
      (footprint "CHIP_R_0603")
      (description "RES SMD 100K OHM 1% 1/10W 0603")
      (fields
        (field (name "MANUFACTURER") "Vishay")
        (field (name "MANUFACTURER PART NUMBER") "CRCW0603100KFKEA")
      )
      (libsource (lib "Pedals SMD") (part "CRCW0603100KFKEA"))
    )
    (comp (ref "R213")
      (value "150k")
      (footprint "CHIP_R_0603")
      (description "RES SMD 150K OHM 1% 1/10W 0603")
      (fields
        (field (name "MANUFACTURER") "Vishay")
        (field (name "MANUFACTURER PART NUMBER") "CRCW0603150KFKEA")
      )
      (libsource (lib "Pedals SMD") (part "CRCW0603150KFKEA"))
    )
    (comp (ref "R214")
      (value "10k")
      (footprint "CHIP_R_0603")
      (description "RES SMD 10K OHM 1% 1/10W 0603")
      (fields
        (field (name "MANUFACTURER") "Vishay")
        (field (name "MANUFACTURER PART NUMBER") "CRCW060310K0FKEA")
      )
      (libsource (lib "Pedals SMD") (part "CRCW060310K0FKEA"))
    )
    (comp (ref "R215")
      (value "100k")
      (footprint "CHIP_R_0603")
      (description "RES SMD 100K OHM 1% 1/10W 0603")
      (fields
        (field (name "MANUFACTURER") "Vishay")
        (field (name "MANUFACTURER PART NUMBER") "CRCW0603100KFKEA")
      )
      (libsource (lib "Pedals SMD") (part "CRCW0603100KFKEA"))
    )
    (comp (ref "R216")
      (value "10k")
      (footprint "CHIP_R_0603")
      (description "RES SMD 10K OHM 1% 1/10W 0603")
      (fields
        (field (name "MANUFACTURER") "Vishay")
        (field (name "MANUFACTURER PART NUMBER") "CRCW060310K0FKEA")
      )
      (libsource (lib "Pedals SMD") (part "CRCW060310K0FKEA"))
    )
    (comp (ref "R217")
      (value "10k")
      (footprint "CHIP_R_0603")
      (description "RES SMD 10K OHM 1% 1/10W 0603")
      (fields
        (field (name "MANUFACTURER") "Vishay")
        (field (name "MANUFACTURER PART NUMBER") "CRCW060310K0FKEA")
      )
      (libsource (lib "Pedals SMD") (part "CRCW060310K0FKEA"))
    )
    (comp (ref "R218")
      (value "4.7k")
      (footprint "CHIP_R_0603")
      (description "RES SMD 4.7K OHM 1% 1/10W 0603")
      (fields
        (field (name "MANUFACTURER") "Vishay")
        (field (name "MANUFACTURER PART NUMBER") "CRCW06034K70FKEA")
      )
      (libsource (lib "Pedals SMD") (part "CRCW06034K70FKEA"))
    )
    (comp (ref "R219")
      (value "150k")
      (footprint "CHIP_R_0603")
      (description "RES SMD 150K OHM 1% 1/10W 0603")
      (fields
        (field (name "MANUFACTURER") "Vishay")
        (field (name "MANUFACTURER PART NUMBER") "CRCW0603150KFKEA")
      )
      (libsource (lib "Pedals SMD") (part "CRCW0603150KFKEA"))
    )
    (comp (ref "R220")
      (value "51k")
      (footprint "CHIP_R_0603")
      (description "RES SMD 51K OHM 1% 1/10W 0603")
      (fields
        (field (name "MANUFACTURER") "Vishay")
        (field (name "MANUFACTURER PART NUMBER") "CRCW060351K0FKEA")
      )
      (libsource (lib "Pedals SMD") (part "CRCW060351K0FKEA"))
    )
    (comp (ref "R221")
      (value "10k")
      (footprint "CHIP_R_0603")
      (description "RES SMD 10K OHM 1% 1/10W 0603")
      (fields
        (field (name "MANUFACTURER") "Vishay")
        (field (name "MANUFACTURER PART NUMBER") "CRCW060310K0FKEA")
      )
      (libsource (lib "Pedals SMD") (part "CRCW060310K0FKEA"))
    )
    (comp (ref "R222")
      (value "100R")
      (footprint "CHIP_R_0603")
      (description "RES SMD 100 OHM 1% 1/10W 0603")
      (fields
        (field (name "MANUFACTURER") "Vishay Dale")
        (field (name "MANUFACTURER PART NUMBER") "CRCW0603100RFKEA")
      )
      (libsource (lib "Pedals SMD") (part "CRCW0603100RFKEA"))
    )
    (comp (ref "R223")
      (value "3.9M")
      (footprint "CHIP_R_0603")
      (description "RES SMD 3.9M OHM 1% 1/10W 0603")
      (fields
        (field (name "MANUFACTURER") "Vishay")
        (field (name "MANUFACTURER PART NUMBER") "CRCW06033M90FKEA")
      )
      (libsource (lib "Pedals SMD") (part "CRCW06033M90FKEA"))
    )
    (comp (ref "R224")
      (value "100k")
      (footprint "CHIP_R_0603")
      (description "RES SMD 100K OHM 1% 1/10W 0603")
      (fields
        (field (name "MANUFACTURER") "Vishay")
        (field (name "MANUFACTURER PART NUMBER") "CRCW0603100KFKEA")
      )
      (libsource (lib "Pedals SMD") (part "CRCW0603100KFKEA"))
    )
    (comp (ref "R225")
      (value "1M")
      (footprint "CHIP_R_0603")
      (description "RES SMD 1M OHM 1% 1/10W 0603")
      (fields
        (field (name "MANUFACTURER") "Vishay")
        (field (name "MANUFACTURER PART NUMBER") "CRCW06031M00FKEA")
      )
      (libsource (lib "Pedals SMD") (part "CRCW06031M00FKEA"))
    )
    (comp (ref "R226")
      (value "100R")
      (footprint "CHIP_R_0603")
      (description "RES SMD 100 OHM 1% 1/10W 0603")
      (fields
        (field (name "MANUFACTURER") "Vishay Dale")
        (field (name "MANUFACTURER PART NUMBER") "CRCW0603100RFKEA")
      )
      (libsource (lib "Pedals SMD") (part "CRCW0603100RFKEA"))
    )
    (comp (ref "R227")
      (value "100k")
      (footprint "CHIP_R_0603")
      (description "RES SMD 100K OHM 1% 1/10W 0603")
      (fields
        (field (name "MANUFACTURER") "Vishay")
        (field (name "MANUFACTURER PART NUMBER") "CRCW0603100KFKEA")
      )
      (libsource (lib "Pedals SMD") (part "CRCW0603100KFKEA"))
    )
    (comp (ref "REG1")
      (value "78L05")
      (footprint "SOT23-3")
      (description "TAIWAN SEMICONDUCTOR - TS78L05CX RFG - REG 3-TERMINAL 100MA, SMD, SOT23-3")
      (fields
        (field (name "MANUFACTURER") "Taiwan Semiconductor")
        (field (name "MANUFACTURER PART NUMBER") "TS78L05CXRFG")
      )
      (libsource (lib "Pedals SMD") (part "TS78L05CXRFG"))
    )
    (comp (ref "SUSTAIN")
      (value "500kC")
      (footprint "ALPHA_9MM_TOP_NOMH")
      (description "500k Anti Log potentiometer round shaft")
      (libsource (lib "Pedals") (part "POT_500kC_ALPHA_9mm"))
    )
    (comp (ref "U1")
      (value "ATTINY84")
      (footprint "SO-14")
      (description "MCU 8-bit ATtiny AVR RISC 8KB Flash 2.5V/3.3V/5V 14-Pin SOIC")
      (fields
        (field (name "MANUFACTURER") "Microchip / Atmel")
        (field (name "MANUFACTURER PART NUMBER") "ATTINY84A-SSU")
      )
      (libsource (lib "Pedals SMD") (part "ATTINY84A-SSU"))
    )
    (comp (ref "VOLUME")
      (value "50kA")
      (footprint "ALPHA_9MM_TOP_NOMH")
      (description "50k Log potentiometer round shaft")
      (libsource (lib "Pedals") (part "POT_50kA_ALPHA_9mm"))
    )
  )
  (nets
    (net (code "1") (name "+5V") (class "Default")
      (node (ref "C3") (pin "1") (pinfunction "1_1") (pintype "passive"))
      (node (ref "C4") (pin "+") (pinfunction "+_+") (pintype "passive"))
      (node (ref "C5") (pin "1") (pinfunction "1_1") (pintype "passive"))
      (node (ref "D2") (pin "1") (pinfunction "1_1") (pintype "passive"))
      (node (ref "D3") (pin "1") (pinfunction "1_1") (pintype "passive"))
      (node (ref "K1") (pin "1") (pinfunction "+_1") (pintype "passive"))
      (node (ref "K2") (pin "1") (pinfunction "+_1") (pintype "passive"))
      (node (ref "PROG") (pin "5") (pinfunction "5_5") (pintype "passive"))
      (node (ref "REG1") (pin "1") (pinfunction "OUTPUT_1") (pintype "power_in"))
      (node (ref "U1") (pin "1") (pinfunction "VCC_1") (pintype "power_in"))
    )
    (net (code "2") (name "+9V") (class "Default")
      (node (ref "C1") (pin "+") (pinfunction "+_+") (pintype "passive"))
      (node (ref "C2") (pin "1") (pinfunction "1_1") (pintype "passive"))
      (node (ref "D1") (pin "1") (pinfunction "1_1") (pintype "passive"))
      (node (ref "DC") (pin "1") (pinfunction "S_1") (pintype "passive"))
      (node (ref "R101") (pin "1") (pinfunction "1_1") (pintype "passive"))
      (node (ref "R201") (pin "1") (pinfunction "1_1") (pintype "passive"))
      (node (ref "REG1") (pin "2") (pinfunction "INPUT_2") (pintype "power_in"))
    )
    (net (code "3") (name "/IN") (class "Default")
      (node (ref "INPUT") (pin "T") (pinfunction "T_T") (pintype "passive"))
      (node (ref "K1") (pin "6") (pinfunction "P_6") (pintype "passive"))
    )
    (net (code "4") (name "/OUT") (class "Default")
      (node (ref "K1") (pin "3") (pinfunction "P_3") (pintype "passive"))
      (node (ref "OK1") (pin "6") (pinfunction "COL_6") (pintype "passive"))
      (node (ref "OUTPUT") (pin "T") (pinfunction "T_T") (pintype "passive"))
    )
    (net (code "5") (name "/PA0") (class "Default")
      (node (ref "R5") (pin "1") (pinfunction "1_1") (pintype "passive"))
      (node (ref "U1") (pin "13") (pinfunction "PA0_13") (pintype "bidirectional"))
    )
    (net (code "6") (name "/PA1") (class "Default")
      (node (ref "R4") (pin "1") (pinfunction "1_1") (pintype "passive"))
      (node (ref "U1") (pin "12") (pinfunction "PA1_12") (pintype "bidirectional"))
    )
    (net (code "7") (name "/PA2") (class "Default")
      (node (ref "R6") (pin "1") (pinfunction "1_1") (pintype "passive"))
      (node (ref "U1") (pin "11") (pinfunction "PA2_11") (pintype "bidirectional"))
    )
    (net (code "8") (name "/PA3") (class "Default")
      (node (ref "R1") (pin "1") (pinfunction "1_1") (pintype "passive"))
      (node (ref "U1") (pin "10") (pinfunction "PA3_10") (pintype "bidirectional"))
    )
    (net (code "9") (name "/PA4") (class "Default")
      (node (ref "PROG") (pin "2") (pinfunction "2_2") (pintype "passive"))
      (node (ref "R2") (pin "1") (pinfunction "1_1") (pintype "passive"))
      (node (ref "U1") (pin "9") (pinfunction "PA4_9") (pintype "bidirectional"))
    )
    (net (code "10") (name "/PA5") (class "Default")
      (node (ref "FSW1") (pin "1") (pinfunction "S_1") (pintype "passive"))
      (node (ref "PROG") (pin "1") (pinfunction "1_1") (pintype "passive"))
      (node (ref "U1") (pin "8") (pinfunction "PA5_8") (pintype "bidirectional"))
    )
    (net (code "11") (name "/PA6") (class "Default")
      (node (ref "MODE") (pin "A1") (pinfunction "A1_A1") (pintype "passive"))
      (node (ref "PROG") (pin "4") (pinfunction "4_4") (pintype "passive"))
      (node (ref "U1") (pin "7") (pinfunction "PA6_7") (pintype "bidirectional"))
    )
    (net (code "12") (name "/PA7") (class "Default")
      (node (ref "MODE") (pin "B1") (pinfunction "B1_B1") (pintype "passive"))
      (node (ref "U1") (pin "6") (pinfunction "PA7_6") (pintype "bidirectional"))
    )
    (net (code "13") (name "/PB0") (class "Default")
      (node (ref "FSW2") (pin "1") (pinfunction "S_1") (pintype "passive"))
      (node (ref "U1") (pin "2") (pinfunction "PB0_2") (pintype "bidirectional"))
    )
    (net (code "14") (name "/PB1") (class "Default")
      (node (ref "R3") (pin "1") (pinfunction "1_1") (pintype "passive"))
      (node (ref "U1") (pin "3") (pinfunction "PB1_3") (pintype "bidirectional"))
    )
    (net (code "15") (name "/PB2") (class "Default")
      (node (ref "MODE") (pin "C1") (pinfunction "C1_C1") (pintype "passive"))
      (node (ref "U1") (pin "5") (pinfunction "PB2_5") (pintype "bidirectional"))
    )
    (net (code "16") (name "/PB3") (class "Default")
      (node (ref "PROG") (pin "3") (pinfunction "3_3") (pintype "passive"))
      (node (ref "U1") (pin "4") (pinfunction "PB3_4") (pintype "bidirectional"))
    )
    (net (code "17") (name "/RETURN") (class "Default")
      (node (ref "K1") (pin "4") (pinfunction "S_4") (pintype "passive"))
      (node (ref "K2") (pin "3") (pinfunction "P_3") (pintype "passive"))
    )
    (net (code "18") (name "/RETURN1") (class "Default")
      (node (ref "K2") (pin "2") (pinfunction "O_2") (pintype "passive"))
      (node (ref "LEVEL") (pin "2") (pinfunction "2_2") (pintype "passive"))
    )
    (net (code "19") (name "/RETURN2") (class "Default")
      (node (ref "C216") (pin "-") (pinfunction "-_-") (pintype "passive"))
      (node (ref "K2") (pin "4") (pinfunction "S_4") (pintype "passive"))
      (node (ref "R227") (pin "2") (pinfunction "2_2") (pintype "passive"))
    )
    (net (code "20") (name "/SEND") (class "Default")
      (node (ref "K1") (pin "5") (pinfunction "S_5") (pintype "passive"))
      (node (ref "K2") (pin "6") (pinfunction "P_6") (pintype "passive"))
    )
    (net (code "21") (name "/SEND1") (class "Default")
      (node (ref "C106") (pin "2") (pinfunction "2_2") (pintype "passive"))
      (node (ref "K2") (pin "7") (pinfunction "O_7") (pintype "passive"))
      (node (ref "R106") (pin "2") (pinfunction "2_2") (pintype "passive"))
    )
    (net (code "22") (name "/SEND2") (class "Default")
      (node (ref "K2") (pin "5") (pinfunction "S_5") (pintype "passive"))
      (node (ref "R204") (pin "2") (pinfunction "2_2") (pintype "passive"))
      (node (ref "R205") (pin "1") (pinfunction "1_1") (pintype "passive"))
    )
    (net (code "23") (name "GND") (class "Default")
      (node (ref "C1") (pin "-") (pinfunction "-_-") (pintype "passive"))
      (node (ref "C101") (pin "-") (pinfunction "-_-") (pintype "passive"))
      (node (ref "C102") (pin "-") (pinfunction "-_-") (pintype "passive"))
      (node (ref "C103") (pin "-") (pinfunction "-_-") (pintype "passive"))
      (node (ref "C104") (pin "2") (pinfunction "2_2") (pintype "passive"))
      (node (ref "C105") (pin "2") (pinfunction "2_2") (pintype "passive"))
      (node (ref "C109") (pin "-") (pinfunction "-_-") (pintype "passive"))
      (node (ref "C112") (pin "-") (pinfunction "-_-") (pintype "passive"))
      (node (ref "C2") (pin "2") (pinfunction "2_2") (pintype "passive"))
      (node (ref "C201") (pin "-") (pinfunction "-_-") (pintype "passive"))
      (node (ref "C202") (pin "-") (pinfunction "-_-") (pintype "passive"))
      (node (ref "C203") (pin "2") (pinfunction "2_2") (pintype "passive"))
      (node (ref "C204") (pin "2") (pinfunction "2_2") (pintype "passive"))
      (node (ref "C209") (pin "-") (pinfunction "-_-") (pintype "passive"))
      (node (ref "C3") (pin "2") (pinfunction "2_2") (pintype "passive"))
      (node (ref "C4") (pin "-") (pinfunction "-_-") (pintype "passive"))
      (node (ref "C5") (pin "2") (pinfunction "2_2") (pintype "passive"))
      (node (ref "D1") (pin "2") (pinfunction "2_2") (pintype "passive"))
      (node (ref "D101") (pin "2") (pinfunction "2_2") (pintype "passive"))
      (node (ref "D102") (pin "2") (pinfunction "2_2") (pintype "passive"))
      (node (ref "DC") (pin "2") (pinfunction "S_2") (pintype "passive"))
      (node (ref "FSW1") (pin "2") (pinfunction "S_2") (pintype "passive"))
      (node (ref "FSW2") (pin "2") (pinfunction "S_2") (pintype "passive"))
      (node (ref "IC101") (pin "13") (pinfunction "IN_N_13") (pintype "passive"))
      (node (ref "IC101") (pin "14") (pinfunction "IN_P_14") (pintype "passive"))
      (node (ref "IC101") (pin "6") (pinfunction "V-_6") (pintype "power_in"))
      (node (ref "IC102") (pin "4") (pinfunction "V-_4") (pintype "power_in"))
      (node (ref "IC201") (pin "11") (pinfunction "V-_11") (pintype "power_in"))
      (node (ref "IC202") (pin "13") (pinfunction "IN_N_13") (pintype "passive"))
      (node (ref "IC202") (pin "14") (pinfunction "IN_P_14") (pintype "passive"))
      (node (ref "IC202") (pin "6") (pinfunction "V-_6") (pintype "power_in"))
      (node (ref "INPUT") (pin "S") (pinfunction "S_S") (pintype "passive"))
      (node (ref "LED1") (pin "1") (pinfunction "S_1") (pintype "passive"))
      (node (ref "LED2") (pin "2") (pinfunction "S_2") (pintype "passive"))
      (node (ref "LEVEL") (pin "1") (pinfunction "1_1") (pintype "passive"))
      (node (ref "MODE") (pin "A2") (pinfunction "A2_A2") (pintype "passive"))
      (node (ref "MODE") (pin "B2") (pinfunction "B2_B2") (pintype "passive"))
      (node (ref "MODE") (pin "C2") (pinfunction "C2_C2") (pintype "passive"))
      (node (ref "OK1") (pin "3") (pinfunction "C_3") (pintype "passive"))
      (node (ref "OK1") (pin "4") (pinfunction "EMIT_4") (pintype "passive"))
      (node (ref "OUTPUT") (pin "S") (pinfunction "S_S") (pintype "passive"))
      (node (ref "PROG") (pin "6") (pinfunction "6_6") (pintype "passive"))
      (node (ref "Q1") (pin "2") (pinfunction "E_2") (pintype "passive"))
      (node (ref "Q103") (pin "2") (pinfunction "E_2") (pintype "passive"))
      (node (ref "Q104") (pin "2") (pinfunction "E_2") (pintype "passive"))
      (node (ref "Q2") (pin "2") (pinfunction "E_2") (pintype "passive"))
      (node (ref "Q203") (pin "3") (pinfunction "C_3") (pintype "passive"))
      (node (ref "R103") (pin "1") (pinfunction "1_1") (pintype "passive"))
      (node (ref "R105") (pin "1") (pinfunction "1_1") (pintype "passive"))
      (node (ref "R106") (pin "1") (pinfunction "1_1") (pintype "passive"))
      (node (ref "R109") (pin "1") (pinfunction "1_1") (pintype "passive"))
      (node (ref "R110") (pin "1") (pinfunction "1_1") (pintype "passive"))
      (node (ref "R114") (pin "1") (pinfunction "1_1") (pintype "passive"))
      (node (ref "R118") (pin "1") (pinfunction "1_1") (pintype "passive"))
      (node (ref "R119") (pin "1") (pinfunction "1_1") (pintype "passive"))
      (node (ref "R123") (pin "1") (pinfunction "1_1") (pintype "passive"))
      (node (ref "R126") (pin "1") (pinfunction "1_1") (pintype "passive"))
      (node (ref "R203") (pin "1") (pinfunction "1_1") (pintype "passive"))
      (node (ref "R204") (pin "1") (pinfunction "1_1") (pintype "passive"))
      (node (ref "R209") (pin "1") (pinfunction "1_1") (pintype "passive"))
      (node (ref "R212") (pin "1") (pinfunction "1_1") (pintype "passive"))
      (node (ref "R214") (pin "1") (pinfunction "1_1") (pintype "passive"))
      (node (ref "R218") (pin "1") (pinfunction "1_1") (pintype "passive"))
      (node (ref "R220") (pin "1") (pinfunction "1_1") (pintype "passive"))
      (node (ref "R227") (pin "1") (pinfunction "1_1") (pintype "passive"))
      (node (ref "REG1") (pin "3") (pinfunction "COMMON_3") (pintype "power_in"))
      (node (ref "SUSTAIN") (pin "1") (pinfunction "1_1") (pintype "passive"))
      (node (ref "U1") (pin "14") (pinfunction "GND_14") (pintype "passive"))
      (node (ref "VOLUME") (pin "1") (pinfunction "1_1") (pintype "passive"))
    )
    (net (code "24") (name "Net-(ATTACK-Pad2)") (class "Default")
      (node (ref "ATTACK") (pin "2") (pinfunction "2_2") (pintype "passive"))
      (node (ref "R121") (pin "1") (pinfunction "1_1") (pintype "passive"))
      (node (ref "R122") (pin "2") (pinfunction "2_2") (pintype "passive"))
    )
    (net (code "25") (name "Net-(ATTACK-Pad3)") (class "Default")
      (node (ref "ATTACK") (pin "3") (pinfunction "3_3") (pintype "passive"))
      (node (ref "R120") (pin "1") (pinfunction "1_1") (pintype "passive"))
      (node (ref "R121") (pin "2") (pinfunction "2_2") (pintype "passive"))
    )
    (net (code "26") (name "Net-(BLEND-Pad1)") (class "Default")
      (node (ref "BLEND") (pin "1") (pinfunction "1_1") (pintype "passive"))
      (node (ref "R130") (pin "2") (pinfunction "2_2") (pintype "passive"))
      (node (ref "R132") (pin "1") (pinfunction "1_1") (pintype "passive"))
    )
    (net (code "27") (name "Net-(BLEND-Pad3)") (class "Default")
      (node (ref "BLEND") (pin "3") (pinfunction "3_3") (pintype "passive"))
      (node (ref "R129") (pin "2") (pinfunction "2_2") (pintype "passive"))
      (node (ref "R131") (pin "1") (pinfunction "1_1") (pintype "passive"))
    )
    (net (code "28") (name "Net-(C106-Pad1)") (class "Default")
      (node (ref "C106") (pin "1") (pinfunction "1_1") (pintype "passive"))
      (node (ref "R107") (pin "2") (pinfunction "2_2") (pintype "passive"))
    )
    (net (code "29") (name "Net-(C108-Pad2)") (class "Default")
      (node (ref "C108") (pin "2") (pinfunction "2_2") (pintype "passive"))
      (node (ref "C109") (pin "+") (pinfunction "+_+") (pintype "passive"))
      (node (ref "R115") (pin "1") (pinfunction "1_1") (pintype "passive"))
    )
    (net (code "30") (name "Net-(C114-Pad1)") (class "Default")
      (node (ref "C114") (pin "1") (pinfunction "1_1") (pintype "passive"))
      (node (ref "R125") (pin "2") (pinfunction "2_2") (pintype "passive"))
    )
    (net (code "31") (name "Net-(C115-Pad-)") (class "Default")
      (node (ref "C115") (pin "-") (pinfunction "-_-") (pintype "passive"))
      (node (ref "R127") (pin "1") (pinfunction "1_1") (pintype "passive"))
    )
    (net (code "32") (name "Net-(C117-Pad-)") (class "Default")
      (node (ref "C117") (pin "-") (pinfunction "-_-") (pintype "passive"))
      (node (ref "LEVEL") (pin "3") (pinfunction "3_3") (pintype "passive"))
    )
    (net (code "33") (name "Net-(C205-Pad2)") (class "Default")
      (node (ref "C205") (pin "2") (pinfunction "2_2") (pintype "passive"))
      (node (ref "R205") (pin "2") (pinfunction "2_2") (pintype "passive"))
    )
    (net (code "34") (name "Net-(C206-Pad-)") (class "Default")
      (node (ref "C206") (pin "-") (pinfunction "-_-") (pintype "passive"))
      (node (ref "R207") (pin "1") (pinfunction "1_1") (pintype "passive"))
    )
    (net (code "35") (name "Net-(C212-Pad+)") (class "Default")
      (node (ref "C212") (pin "+") (pinfunction "+_+") (pintype "passive"))
      (node (ref "R222") (pin "1") (pinfunction "1_1") (pintype "passive"))
    )
    (net (code "36") (name "Net-(C213-Pad-)") (class "Default")
      (node (ref "C213") (pin "-") (pinfunction "-_-") (pintype "passive"))
      (node (ref "SUSTAIN") (pin "3") (pinfunction "3_3") (pintype "passive"))
      (node (ref "VOLUME") (pin "3") (pinfunction "3_3") (pintype "passive"))
    )
    (net (code "37") (name "Net-(C214-Pad+)") (class "Default")
      (node (ref "C214") (pin "+") (pinfunction "+_+") (pintype "passive"))
      (node (ref "R224") (pin "2") (pinfunction "2_2") (pintype "passive"))
    )
    (net (code "38") (name "Net-(C214-Pad-)") (class "Default")
      (node (ref "C214") (pin "-") (pinfunction "-_-") (pintype "passive"))
      (node (ref "SUSTAIN") (pin "2") (pinfunction "2_2") (pintype "passive"))
    )
    (net (code "39") (name "Net-(C215-Pad2)") (class "Default")
      (node (ref "C215") (pin "2") (pinfunction "2_2") (pintype "passive"))
      (node (ref "VOLUME") (pin "2") (pinfunction "2_2") (pintype "passive"))
    )
    (net (code "40") (name "Net-(C216-Pad+)") (class "Default")
      (node (ref "C216") (pin "+") (pinfunction "+_+") (pintype "passive"))
      (node (ref "R226") (pin "2") (pinfunction "2_2") (pintype "passive"))
    )
    (net (code "41") (name "Net-(COMP-Pad3)") (class "Default")
      (node (ref "COMP") (pin "3") (pinfunction "3_3") (pintype "passive"))
      (node (ref "R124") (pin "2") (pinfunction "2_2") (pintype "passive"))
    )
    (net (code "42") (name "Net-(D201-Pad1)") (class "Default")
      (node (ref "D201") (pin "1") (pinfunction "1_1") (pintype "passive"))
      (node (ref "R211") (pin "2") (pinfunction "2_2") (pintype "passive"))
    )
    (net (code "43") (name "Net-(IC101A-IN_N)") (class "Default")
      (node (ref "C107") (pin "+") (pinfunction "+_+") (pintype "passive"))
      (node (ref "IC101") (pin "4") (pinfunction "IN_N_4") (pintype "passive"))
      (node (ref "R110") (pin "2") (pinfunction "2_2") (pintype "passive"))
      (node (ref "R111") (pin "1") (pinfunction "1_1") (pintype "passive"))
    )
    (net (code "44") (name "Net-(IC101A-IN_P)") (class "Default")
      (node (ref "C108") (pin "1") (pinfunction "1_1") (pintype "passive"))
      (node (ref "IC101") (pin "3") (pinfunction "IN_P_3") (pintype "passive"))
      (node (ref "R113") (pin "2") (pinfunction "2_2") (pintype "passive"))
      (node (ref "R114") (pin "2") (pinfunction "2_2") (pintype "passive"))
      (node (ref "R115") (pin "2") (pinfunction "2_2") (pintype "passive"))
    )
    (net (code "45") (name "Net-(IC101A-I_BIAS)") (class "Default")
      (node (ref "IC101") (pin "1") (pinfunction "I_BIAS_1") (pintype "passive"))
      (node (ref "R124") (pin "1") (pinfunction "1_1") (pintype "passive"))
    )
    (net (code "46") (name "Net-(IC101A-OUT)") (class "Default")
      (node (ref "C110") (pin "2") (pinfunction "2_2") (pintype "passive"))
      (node (ref "IC101") (pin "5") (pinfunction "OUT_5") (pintype "output"))
      (node (ref "Q102") (pin "1") (pinfunction "B_1") (pintype "passive"))
      (node (ref "R116") (pin "1") (pinfunction "1_1") (pintype "passive"))
    )
    (net (code "47") (name "Net-(IC102A--IN)") (class "Default")
      (node (ref "IC102") (pin "2") (pinfunction "-IN_2") (pintype "input"))
      (node (ref "R131") (pin "2") (pinfunction "2_2") (pintype "passive"))
      (node (ref "R132") (pin "2") (pinfunction "2_2") (pintype "passive"))
      (node (ref "R133") (pin "1") (pinfunction "1_1") (pintype "passive"))
    )
    (net (code "48") (name "Net-(IC102A-OUT)") (class "Default")
      (node (ref "C117") (pin "+") (pinfunction "+_+") (pintype "passive"))
      (node (ref "IC102") (pin "1") (pinfunction "OUT_1") (pintype "output"))
      (node (ref "R133") (pin "2") (pinfunction "2_2") (pintype "passive"))
    )
    (net (code "49") (name "Net-(IC102B--IN)") (class "Default")
      (node (ref "C116") (pin "2") (pinfunction "2_2") (pintype "passive"))
      (node (ref "IC102") (pin "6") (pinfunction "-IN_6") (pintype "input"))
      (node (ref "R127") (pin "2") (pinfunction "2_2") (pintype "passive"))
      (node (ref "R128") (pin "1") (pinfunction "1_1") (pintype "passive"))
    )
    (net (code "50") (name "Net-(IC102B-OUT)") (class "Default")
      (node (ref "C116") (pin "1") (pinfunction "1_1") (pintype "passive"))
      (node (ref "IC102") (pin "7") (pinfunction "OUT_7") (pintype "output"))
      (node (ref "R128") (pin "2") (pinfunction "2_2") (pintype "passive"))
      (node (ref "R130") (pin "1") (pinfunction "1_1") (pintype "passive"))
    )
    (net (code "51") (name "Net-(IC201A-+IN)") (class "Default")
      (node (ref "C215") (pin "1") (pinfunction "1_1") (pintype "passive"))
      (node (ref "IC201") (pin "3") (pinfunction "+IN_3") (pintype "passive"))
      (node (ref "R225") (pin "1") (pinfunction "1_1") (pintype "passive"))
    )
    (net (code "52") (name "Net-(IC201A--IN)") (class "Default")
      (node (ref "IC201") (pin "1") (pinfunction "OUT_1") (pintype "output"))
      (node (ref "IC201") (pin "2") (pinfunction "-IN_2") (pintype "passive"))
      (node (ref "R226") (pin "1") (pinfunction "1_1") (pintype "passive"))
    )
    (net (code "53") (name "Net-(IC201B-+IN)") (class "Default")
      (node (ref "C202") (pin "+") (pinfunction "+_+") (pintype "passive"))
      (node (ref "IC201") (pin "5") (pinfunction "+IN_5") (pintype "passive"))
      (node (ref "R202") (pin "2") (pinfunction "2_2") (pintype "passive"))
      (node (ref "R203") (pin "2") (pinfunction "2_2") (pintype "passive"))
    )
    (net (code "54") (name "Net-(IC201C-+IN)") (class "Default")
      (node (ref "C205") (pin "1") (pinfunction "1_1") (pintype "passive"))
      (node (ref "IC201") (pin "10") (pinfunction "+IN_10") (pintype "passive"))
      (node (ref "R206") (pin "1") (pinfunction "1_1") (pintype "passive"))
    )
    (net (code "55") (name "Net-(IC201C--IN)") (class "Default")
      (node (ref "C206") (pin "+") (pinfunction "+_+") (pintype "passive"))
      (node (ref "IC201") (pin "8") (pinfunction "OUT_8") (pintype "output"))
      (node (ref "IC201") (pin "9") (pinfunction "-IN_9") (pintype "passive"))
    )
    (net (code "56") (name "Net-(IC201D--IN)") (class "Default")
      (node (ref "C207") (pin "2") (pinfunction "2_2") (pintype "passive"))
      (node (ref "IC201") (pin "13") (pinfunction "-IN_13") (pintype "passive"))
      (node (ref "IC202") (pin "5") (pinfunction "OUT_5") (pintype "output"))
      (node (ref "R207") (pin "2") (pinfunction "2_2") (pintype "passive"))
      (node (ref "R224") (pin "1") (pinfunction "1_1") (pintype "passive"))
    )
    (net (code "57") (name "Net-(IC201D-OUT)") (class "Default")
      (node (ref "C207") (pin "1") (pinfunction "1_1") (pintype "passive"))
      (node (ref "C208") (pin "+") (pinfunction "+_+") (pintype "passive"))
      (node (ref "C211") (pin "+") (pinfunction "+_+") (pintype "passive"))
      (node (ref "C213") (pin "+") (pinfunction "+_+") (pintype "passive"))
      (node (ref "IC201") (pin "14") (pinfunction "OUT_14") (pintype "output"))
      (node (ref "R221") (pin "1") (pinfunction "1_1") (pintype "passive"))
    )
    (net (code "58") (name "Net-(IC202A-IN_P)") (class "Default")
      (node (ref "IC202") (pin "3") (pinfunction "IN_P_3") (pintype "passive"))
      (node (ref "R221") (pin "2") (pinfunction "2_2") (pintype "passive"))
      (node (ref "R222") (pin "2") (pinfunction "2_2") (pintype "passive"))
    )
    (net (code "59") (name "Net-(IC202A-I_BIAS)") (class "Default")
      (node (ref "IC202") (pin "1") (pinfunction "I_BIAS_1") (pintype "passive"))
      (node (ref "Q204") (pin "2") (pinfunction "E_2") (pintype "passive"))
      (node (ref "R223") (pin "2") (pinfunction "2_2") (pintype "passive"))
    )
    (net (code "60") (name "Net-(K1A--)") (class "Default")
      (node (ref "D2") (pin "2") (pinfunction "2_2") (pintype "passive"))
      (node (ref "K1") (pin "8") (pinfunction "-_8") (pintype "passive"))
      (node (ref "Q1") (pin "3") (pinfunction "C_3") (pintype "passive"))
    )
    (net (code "61") (name "Net-(K1B-O)") (class "Default")
      (node (ref "K1") (pin "2") (pinfunction "O_2") (pintype "passive"))
      (node (ref "K1") (pin "7") (pinfunction "O_7") (pintype "passive"))
    )
    (net (code "62") (name "Net-(K2A--)") (class "Default")
      (node (ref "D3") (pin "2") (pinfunction "2_2") (pintype "passive"))
      (node (ref "K2") (pin "8") (pinfunction "-_8") (pintype "passive"))
      (node (ref "Q2") (pin "3") (pinfunction "C_3") (pintype "passive"))
    )
    (net (code "63") (name "Net-(LED1B-S)") (class "Default")
      (node (ref "LED1") (pin "2") (pinfunction "S_2") (pintype "passive"))
      (node (ref "R2") (pin "2") (pinfunction "2_2") (pintype "passive"))
    )
    (net (code "64") (name "Net-(LED1C-S)") (class "Default")
      (node (ref "LED1") (pin "3") (pinfunction "S_3") (pintype "passive"))
      (node (ref "R1") (pin "2") (pinfunction "2_2") (pintype "passive"))
    )
    (net (code "65") (name "Net-(LED2B-S)") (class "Default")
      (node (ref "LED2") (pin "1") (pinfunction "S_1") (pintype "passive"))
      (node (ref "R3") (pin "2") (pinfunction "2_2") (pintype "passive"))
    )
    (net (code "66") (name "Net-(OK1-A)") (class "Default")
      (node (ref "OK1") (pin "1") (pinfunction "A_1") (pintype "passive"))
      (node (ref "R6") (pin "2") (pinfunction "2_2") (pintype "passive"))
    )
    (net (code "67") (name "Net-(Q1-B)") (class "Default")
      (node (ref "Q1") (pin "1") (pinfunction "B_1") (pintype "passive"))
      (node (ref "R4") (pin "2") (pinfunction "2_2") (pintype "passive"))
    )
    (net (code "68") (name "Net-(Q2-B)") (class "Default")
      (node (ref "Q2") (pin "1") (pinfunction "B_1") (pintype "passive"))
      (node (ref "R5") (pin "2") (pinfunction "2_2") (pintype "passive"))
    )
    (net (code "69") (name "Net-(Q101-B)") (class "Default")
      (node (ref "Q101") (pin "1") (pinfunction "B_1") (pintype "passive"))
      (node (ref "R107") (pin "1") (pinfunction "1_1") (pintype "passive"))
      (node (ref "R108") (pin "1") (pinfunction "1_1") (pintype "passive"))
    )
    (net (code "70") (name "Net-(Q101-E)") (class "Default")
      (node (ref "C107") (pin "-") (pinfunction "-_-") (pintype "passive"))
      (node (ref "C115") (pin "+") (pinfunction "+_+") (pintype "passive"))
      (node (ref "Q101") (pin "2") (pinfunction "E_2") (pintype "passive"))
      (node (ref "R109") (pin "2") (pinfunction "2_2") (pintype "passive"))
      (node (ref "R126") (pin "2") (pinfunction "2_2") (pintype "passive"))
    )
    (net (code "71") (name "Net-(Q102-C)") (class "Default")
      (node (ref "C111") (pin "2") (pinfunction "2_2") (pintype "passive"))
      (node (ref "Q102") (pin "3") (pinfunction "C_3") (pintype "passive"))
      (node (ref "R117") (pin "1") (pinfunction "1_1") (pintype "passive"))
    )
    (net (code "72") (name "Net-(Q102-E)") (class "Default")
      (node (ref "C113") (pin "1") (pinfunction "1_1") (pintype "passive"))
      (node (ref "C114") (pin "2") (pinfunction "2_2") (pintype "passive"))
      (node (ref "Q102") (pin "2") (pinfunction "E_2") (pintype "passive"))
      (node (ref "R118") (pin "2") (pinfunction "2_2") (pintype "passive"))
    )
    (net (code "73") (name "Net-(Q103-B)") (class "Default")
      (node (ref "C111") (pin "1") (pinfunction "1_1") (pintype "passive"))
      (node (ref "D101") (pin "1") (pinfunction "1_1") (pintype "passive"))
      (node (ref "Q103") (pin "1") (pinfunction "B_1") (pintype "passive"))
      (node (ref "R119") (pin "2") (pinfunction "2_2") (pintype "passive"))
    )
    (net (code "74") (name "Net-(Q103-C)") (class "Default")
      (node (ref "ATTACK") (pin "1") (pinfunction "1_1") (pintype "passive"))
      (node (ref "C112") (pin "+") (pinfunction "+_+") (pintype "passive"))
      (node (ref "Q103") (pin "3") (pinfunction "C_3") (pintype "passive"))
      (node (ref "Q104") (pin "3") (pinfunction "C_3") (pintype "passive"))
      (node (ref "Q105") (pin "1") (pinfunction "B_1") (pintype "passive"))
      (node (ref "R122") (pin "1") (pinfunction "1_1") (pintype "passive"))
    )
    (net (code "75") (name "Net-(Q104-B)") (class "Default")
      (node (ref "C113") (pin "2") (pinfunction "2_2") (pintype "passive"))
      (node (ref "D102") (pin "1") (pinfunction "1_1") (pintype "passive"))
      (node (ref "Q104") (pin "1") (pinfunction "B_1") (pintype "passive"))
      (node (ref "R123") (pin "2") (pinfunction "2_2") (pintype "passive"))
    )
    (net (code "76") (name "Net-(Q105-E)") (class "Default")
      (node (ref "COMP") (pin "1") (pinfunction "1_1") (pintype "passive"))
      (node (ref "COMP") (pin "2") (pinfunction "2_2") (pintype "passive"))
      (node (ref "Q105") (pin "2") (pinfunction "E_2") (pintype "passive"))
    )
    (net (code "77") (name "Net-(Q201-B)") (class "Default")
      (node (ref "C208") (pin "-") (pinfunction "-_-") (pintype "passive"))
      (node (ref "Q201") (pin "1") (pinfunction "B_1") (pintype "passive"))
      (node (ref "R208") (pin "1") (pinfunction "1_1") (pintype "passive"))
      (node (ref "R209") (pin "2") (pinfunction "2_2") (pintype "passive"))
    )
    (net (code "78") (name "Net-(Q201-E)") (class "Default")
      (node (ref "D201") (pin "2") (pinfunction "2_2") (pintype "passive"))
      (node (ref "Q201") (pin "2") (pinfunction "E_2") (pintype "passive"))
      (node (ref "Q202") (pin "2") (pinfunction "E_2") (pintype "passive"))
      (node (ref "R210") (pin "2") (pinfunction "2_2") (pintype "passive"))
    )
    (net (code "79") (name "Net-(Q202-B)") (class "Default")
      (node (ref "C210") (pin "-") (pinfunction "-_-") (pintype "passive"))
      (node (ref "Q202") (pin "1") (pinfunction "B_1") (pintype "passive"))
      (node (ref "R213") (pin "1") (pinfunction "1_1") (pintype "passive"))
      (node (ref "R214") (pin "2") (pinfunction "2_2") (pintype "passive"))
    )
    (net (code "80") (name "Net-(Q203-B)") (class "Default")
      (node (ref "C209") (pin "+") (pinfunction "+_+") (pintype "passive"))
      (node (ref "Q203") (pin "1") (pinfunction "B_1") (pintype "passive"))
      (node (ref "R210") (pin "1") (pinfunction "1_1") (pintype "passive"))
      (node (ref "R211") (pin "1") (pinfunction "1_1") (pintype "passive"))
      (node (ref "R212") (pin "2") (pinfunction "2_2") (pintype "passive"))
    )
    (net (code "81") (name "Net-(Q203-E)") (class "Default")
      (node (ref "Q203") (pin "2") (pinfunction "E_2") (pintype "passive"))
      (node (ref "Q204") (pin "1") (pinfunction "B_1") (pintype "passive"))
      (node (ref "R215") (pin "1") (pinfunction "1_1") (pintype "passive"))
    )
    (net (code "82") (name "Net-(Q204-C)") (class "Default")
      (node (ref "Q204") (pin "3") (pinfunction "C_3") (pintype "passive"))
      (node (ref "R216") (pin "1") (pinfunction "1_1") (pintype "passive"))
    )
    (net (code "83") (name "Net-(Q205-B)") (class "Default")
      (node (ref "C211") (pin "-") (pinfunction "-_-") (pintype "passive"))
      (node (ref "Q205") (pin "1") (pinfunction "B_1") (pintype "passive"))
      (node (ref "R219") (pin "1") (pinfunction "1_1") (pintype "passive"))
      (node (ref "R220") (pin "2") (pinfunction "2_2") (pintype "passive"))
    )
    (net (code "84") (name "Net-(Q205-C)") (class "Default")
      (node (ref "C210") (pin "+") (pinfunction "+_+") (pintype "passive"))
      (node (ref "Q205") (pin "3") (pinfunction "C_3") (pintype "passive"))
      (node (ref "R217") (pin "1") (pinfunction "1_1") (pintype "passive"))
    )
    (net (code "85") (name "Net-(Q205-E)") (class "Default")
      (node (ref "Q205") (pin "2") (pinfunction "E_2") (pintype "passive"))
      (node (ref "R218") (pin "2") (pinfunction "2_2") (pintype "passive"))
    )
    (net (code "86") (name "Net-(R111-Pad2)") (class "Default")
      (node (ref "R111") (pin "2") (pinfunction "2_2") (pintype "passive"))
      (node (ref "R112") (pin "2") (pinfunction "2_2") (pintype "passive"))
      (node (ref "R113") (pin "1") (pinfunction "1_1") (pintype "passive"))
    )
    (net (code "87") (name "Net-(R125-Pad1)") (class "Default")
      (node (ref "R125") (pin "1") (pinfunction "1_1") (pintype "passive"))
      (node (ref "R129") (pin "1") (pinfunction "1_1") (pintype "passive"))
    )
    (net (code "88") (name "Va1") (class "Default")
      (node (ref "C102") (pin "+") (pinfunction "+_+") (pintype "passive"))
      (node (ref "C110") (pin "1") (pinfunction "1_1") (pintype "passive"))
      (node (ref "R102") (pin "2") (pinfunction "2_2") (pintype "passive"))
      (node (ref "R103") (pin "2") (pinfunction "2_2") (pintype "passive"))
      (node (ref "R108") (pin "2") (pinfunction "2_2") (pintype "passive"))
      (node (ref "R116") (pin "2") (pinfunction "2_2") (pintype "passive"))
    )
    (net (code "89") (name "Vb1") (class "Default")
      (node (ref "BLEND") (pin "2") (pinfunction "2_2") (pintype "passive"))
      (node (ref "C103") (pin "+") (pinfunction "+_+") (pintype "passive"))
      (node (ref "IC102") (pin "3") (pinfunction "+IN_3") (pintype "input"))
      (node (ref "IC102") (pin "5") (pinfunction "+IN_5") (pintype "input"))
      (node (ref "R104") (pin "2") (pinfunction "2_2") (pintype "passive"))
      (node (ref "R105") (pin "2") (pinfunction "2_2") (pintype "passive"))
    )
    (net (code "90") (name "Vb2") (class "Default")
      (node (ref "C212") (pin "-") (pinfunction "-_-") (pintype "passive"))
      (node (ref "IC201") (pin "12") (pinfunction "+IN_12") (pintype "passive"))
      (node (ref "IC201") (pin "6") (pinfunction "-IN_6") (pintype "passive"))
      (node (ref "IC201") (pin "7") (pinfunction "OUT_7") (pintype "output"))
      (node (ref "IC202") (pin "4") (pinfunction "IN_N_4") (pintype "passive"))
      (node (ref "R206") (pin "2") (pinfunction "2_2") (pintype "passive"))
      (node (ref "R223") (pin "1") (pinfunction "1_1") (pintype "passive"))
      (node (ref "R225") (pin "2") (pinfunction "2_2") (pintype "passive"))
    )
    (net (code "91") (name "Vr1") (class "Default")
      (node (ref "C101") (pin "+") (pinfunction "+_+") (pintype "passive"))
      (node (ref "C104") (pin "1") (pinfunction "1_1") (pintype "passive"))
      (node (ref "C105") (pin "1") (pinfunction "1_1") (pintype "passive"))
      (node (ref "IC101") (pin "11") (pinfunction "V+_11") (pintype "power_in"))
      (node (ref "IC102") (pin "8") (pinfunction "V+_8") (pintype "power_in"))
      (node (ref "Q101") (pin "3") (pinfunction "C_3") (pintype "passive"))
      (node (ref "Q105") (pin "3") (pinfunction "C_3") (pintype "passive"))
      (node (ref "R101") (pin "2") (pinfunction "2_2") (pintype "passive"))
      (node (ref "R102") (pin "1") (pinfunction "1_1") (pintype "passive"))
      (node (ref "R104") (pin "1") (pinfunction "1_1") (pintype "passive"))
      (node (ref "R112") (pin "1") (pinfunction "1_1") (pintype "passive"))
      (node (ref "R117") (pin "2") (pinfunction "2_2") (pintype "passive"))
      (node (ref "R120") (pin "2") (pinfunction "2_2") (pintype "passive"))
    )
    (net (code "92") (name "Vr2") (class "Default")
      (node (ref "C201") (pin "+") (pinfunction "+_+") (pintype "passive"))
      (node (ref "C203") (pin "1") (pinfunction "1_1") (pintype "passive"))
      (node (ref "C204") (pin "1") (pinfunction "1_1") (pintype "passive"))
      (node (ref "IC201") (pin "4") (pinfunction "V+_4") (pintype "power_in"))
      (node (ref "IC202") (pin "11") (pinfunction "V+_11") (pintype "power_in"))
      (node (ref "Q201") (pin "3") (pinfunction "C_3") (pintype "passive"))
      (node (ref "Q202") (pin "3") (pinfunction "C_3") (pintype "passive"))
      (node (ref "R201") (pin "2") (pinfunction "2_2") (pintype "passive"))
      (node (ref "R202") (pin "1") (pinfunction "1_1") (pintype "passive"))
      (node (ref "R208") (pin "2") (pinfunction "2_2") (pintype "passive"))
      (node (ref "R213") (pin "2") (pinfunction "2_2") (pintype "passive"))
      (node (ref "R215") (pin "2") (pinfunction "2_2") (pintype "passive"))
      (node (ref "R216") (pin "2") (pinfunction "2_2") (pintype "passive"))
      (node (ref "R217") (pin "2") (pinfunction "2_2") (pintype "passive"))
      (node (ref "R219") (pin "2") (pinfunction "2_2") (pintype "passive"))
    )
    (net (code "93") (name "unconnected-(IC101A-I_DIODE-Pad2)") (class "Default")
      (node (ref "IC101") (pin "2") (pinfunction "I_DIODE_2") (pintype "passive+no_connect"))
    )
    (net (code "94") (name "unconnected-(IC101B-B-Pad7)") (class "Default")
      (node (ref "IC101") (pin "7") (pinfunction "B_7") (pintype "passive+no_connect"))
    )
    (net (code "95") (name "unconnected-(IC101B-E-Pad8)") (class "Default")
      (node (ref "IC101") (pin "8") (pinfunction "E_8") (pintype "passive+no_connect"))
    )
    (net (code "96") (name "unconnected-(IC101C-I_BIAS-Pad16)") (class "Default")
      (node (ref "IC101") (pin "16") (pinfunction "I_BIAS_16") (pintype "passive"))
    )
    (net (code "97") (name "unconnected-(IC101C-I_DIODE-Pad15)") (class "Default")
      (node (ref "IC101") (pin "15") (pinfunction "I_DIODE_15") (pintype "passive"))
    )
    (net (code "98") (name "unconnected-(IC101C-OUT-Pad12)") (class "Default")
      (node (ref "IC101") (pin "12") (pinfunction "OUT_12") (pintype "output"))
    )
    (net (code "99") (name "unconnected-(IC101D-B-Pad10)") (class "Default")
      (node (ref "IC101") (pin "10") (pinfunction "B_10") (pintype "passive"))
    )
    (net (code "100") (name "unconnected-(IC101D-E-Pad9)") (class "Default")
      (node (ref "IC101") (pin "9") (pinfunction "E_9") (pintype "passive"))
    )
    (net (code "101") (name "unconnected-(IC202A-I_DIODE-Pad2)") (class "Default")
      (node (ref "IC202") (pin "2") (pinfunction "I_DIODE_2") (pintype "passive"))
    )
    (net (code "102") (name "unconnected-(IC202B-B-Pad7)") (class "Default")
      (node (ref "IC202") (pin "7") (pinfunction "B_7") (pintype "passive"))
    )
    (net (code "103") (name "unconnected-(IC202B-E-Pad8)") (class "Default")
      (node (ref "IC202") (pin "8") (pinfunction "E_8") (pintype "passive"))
    )
    (net (code "104") (name "unconnected-(IC202C-I_BIAS-Pad16)") (class "Default")
      (node (ref "IC202") (pin "16") (pinfunction "I_BIAS_16") (pintype "passive"))
    )
    (net (code "105") (name "unconnected-(IC202C-I_DIODE-Pad15)") (class "Default")
      (node (ref "IC202") (pin "15") (pinfunction "I_DIODE_15") (pintype "passive"))
    )
    (net (code "106") (name "unconnected-(IC202C-OUT-Pad12)") (class "Default")
      (node (ref "IC202") (pin "12") (pinfunction "OUT_12") (pintype "output"))
    )
    (net (code "107") (name "unconnected-(IC202D-B-Pad10)") (class "Default")
      (node (ref "IC202") (pin "10") (pinfunction "B_10") (pintype "passive"))
    )
    (net (code "108") (name "unconnected-(IC202D-E-Pad9)") (class "Default")
      (node (ref "IC202") (pin "9") (pinfunction "E_9") (pintype "passive"))
    )
    (net (code "109") (name "unconnected-(INPUT-PadR)") (class "Default")
      (node (ref "INPUT") (pin "R") (pinfunction "R_R") (pintype "passive"))
    )
    (net (code "110") (name "unconnected-(INPUT-PadSN)") (class "Default")
      (node (ref "INPUT") (pin "SN") (pinfunction "SN_SN") (pintype "passive"))
    )
    (net (code "111") (name "unconnected-(OUTPUT-PadR)") (class "Default")
      (node (ref "OUTPUT") (pin "R") (pinfunction "R_R") (pintype "passive"))
    )
    (net (code "112") (name "unconnected-(OUTPUT-PadSN)") (class "Default")
      (node (ref "OUTPUT") (pin "SN") (pinfunction "SN_SN") (pintype "passive"))
    )
  )
)
